# bldc-high-current-2-easyeda.net
KiCad netlist of a schematic drawn in EasyEDA Pro
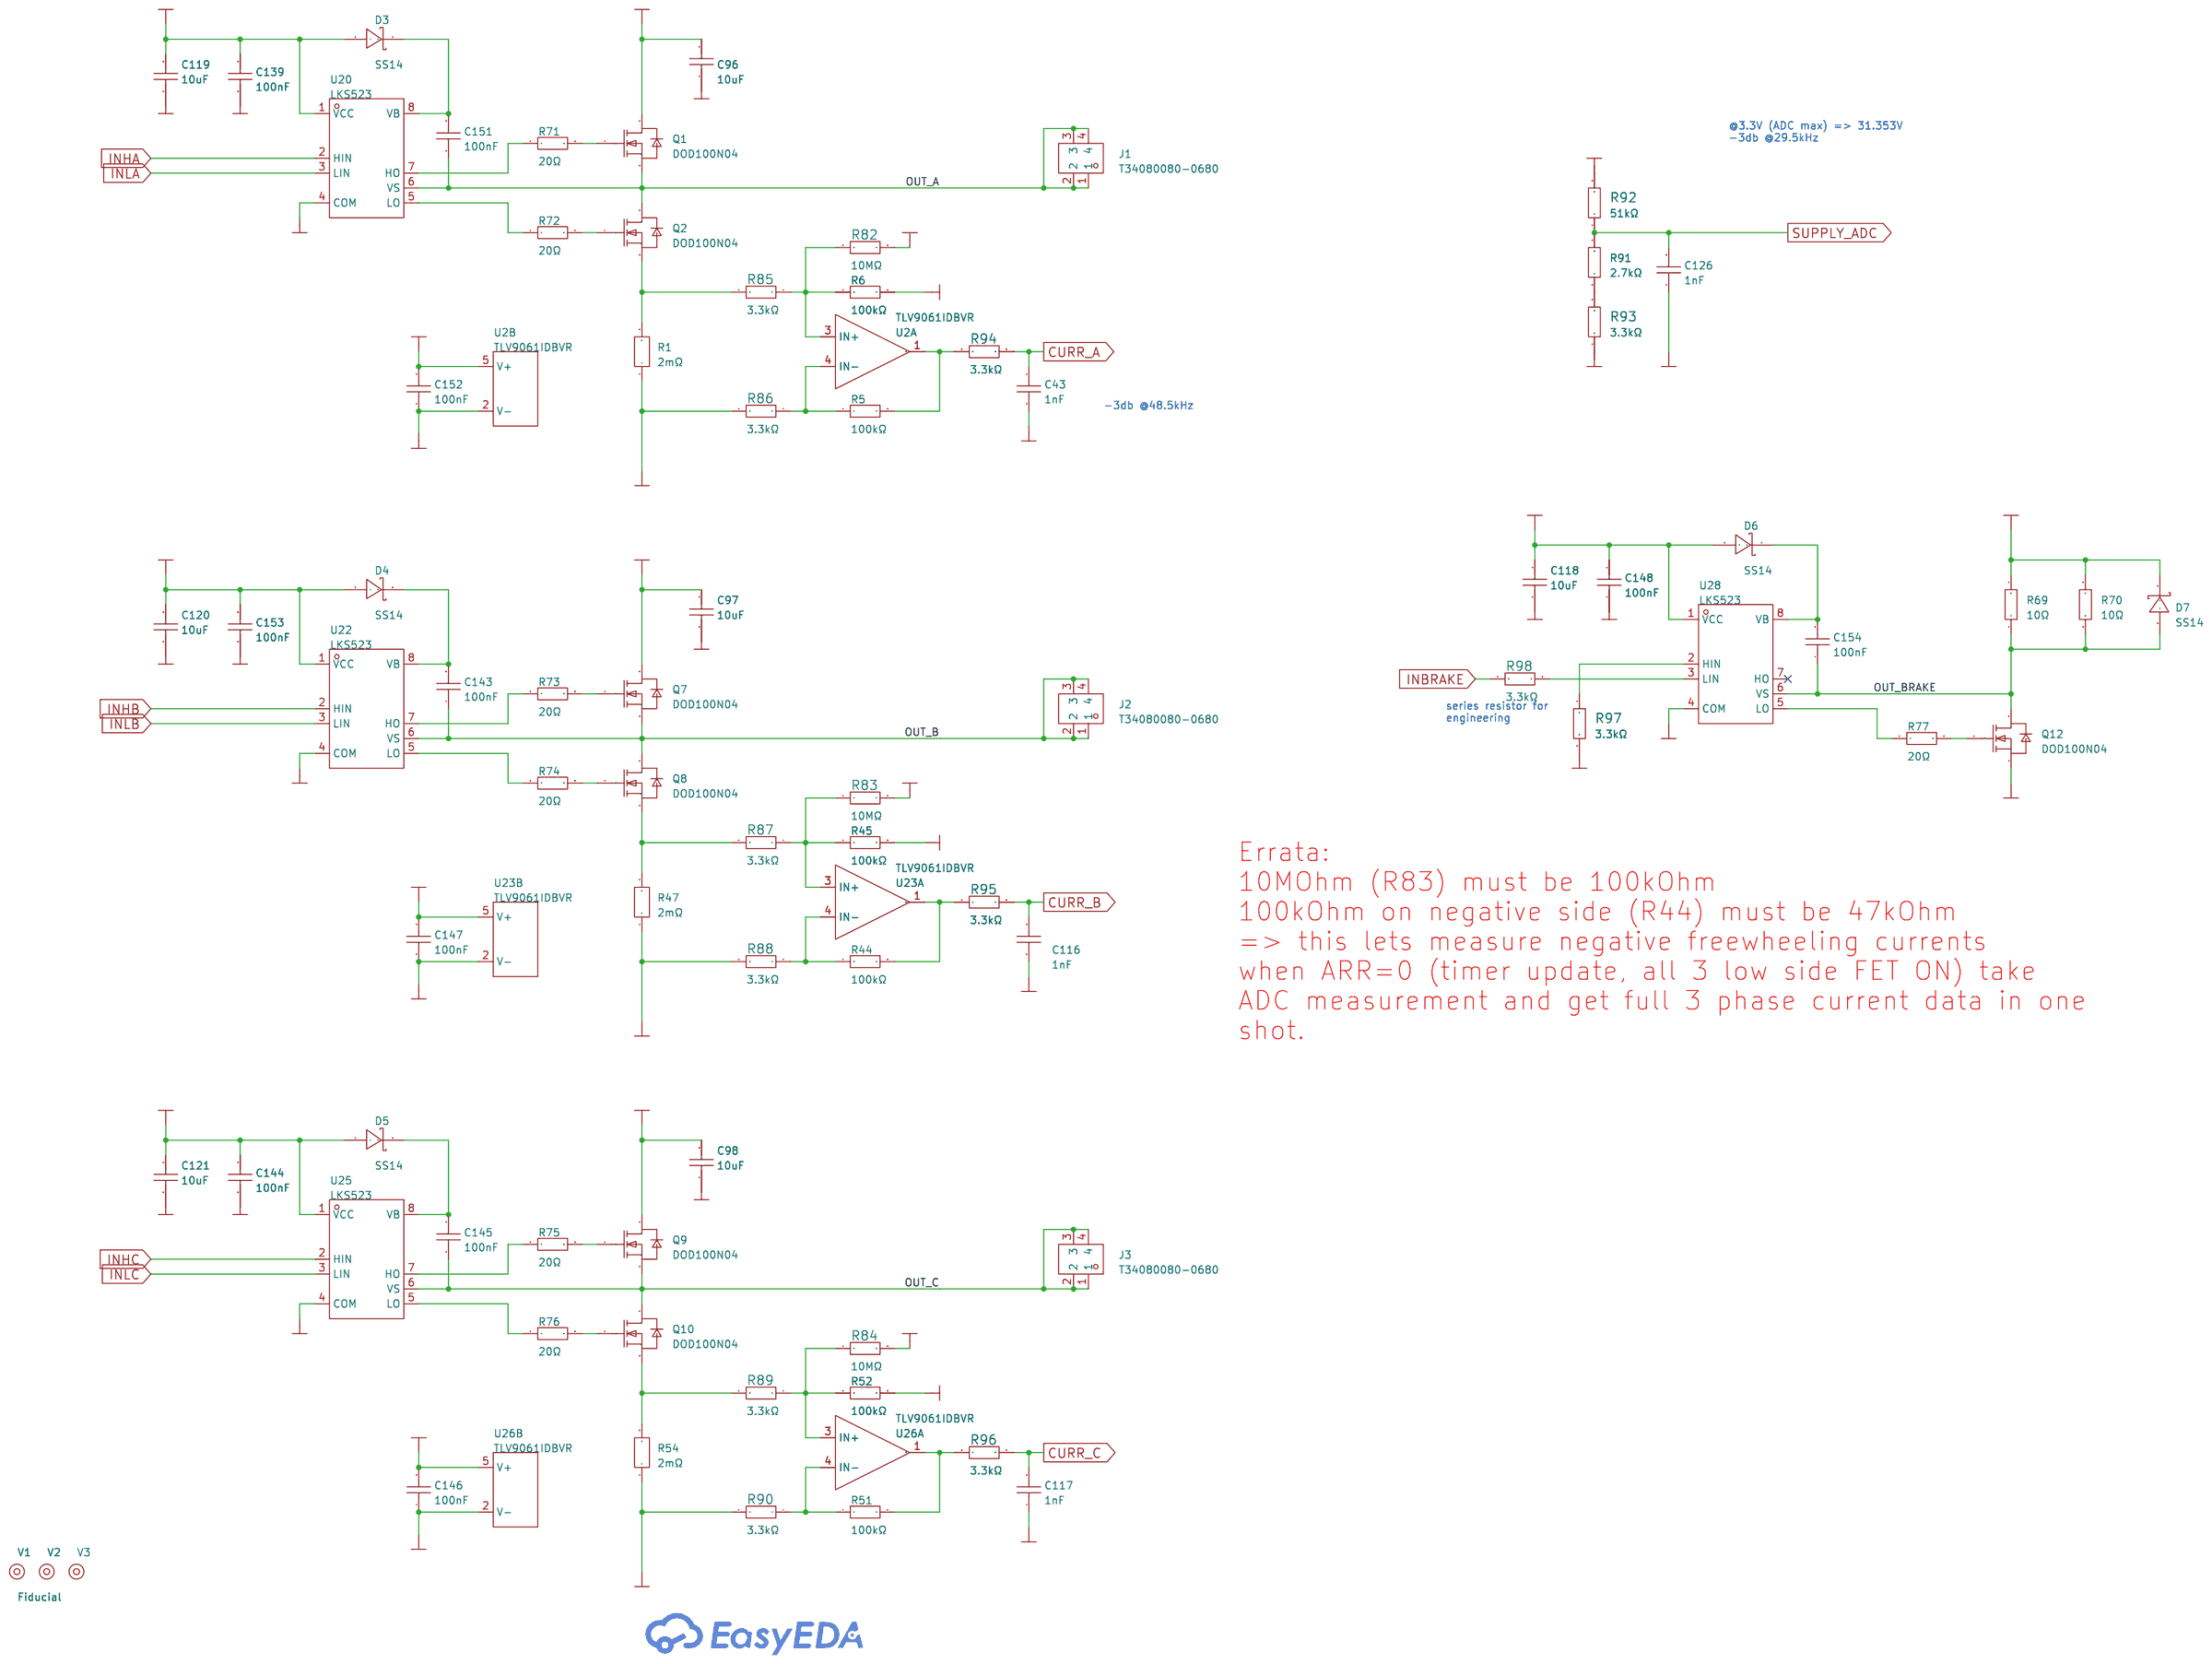
[diagram p0: power stage]
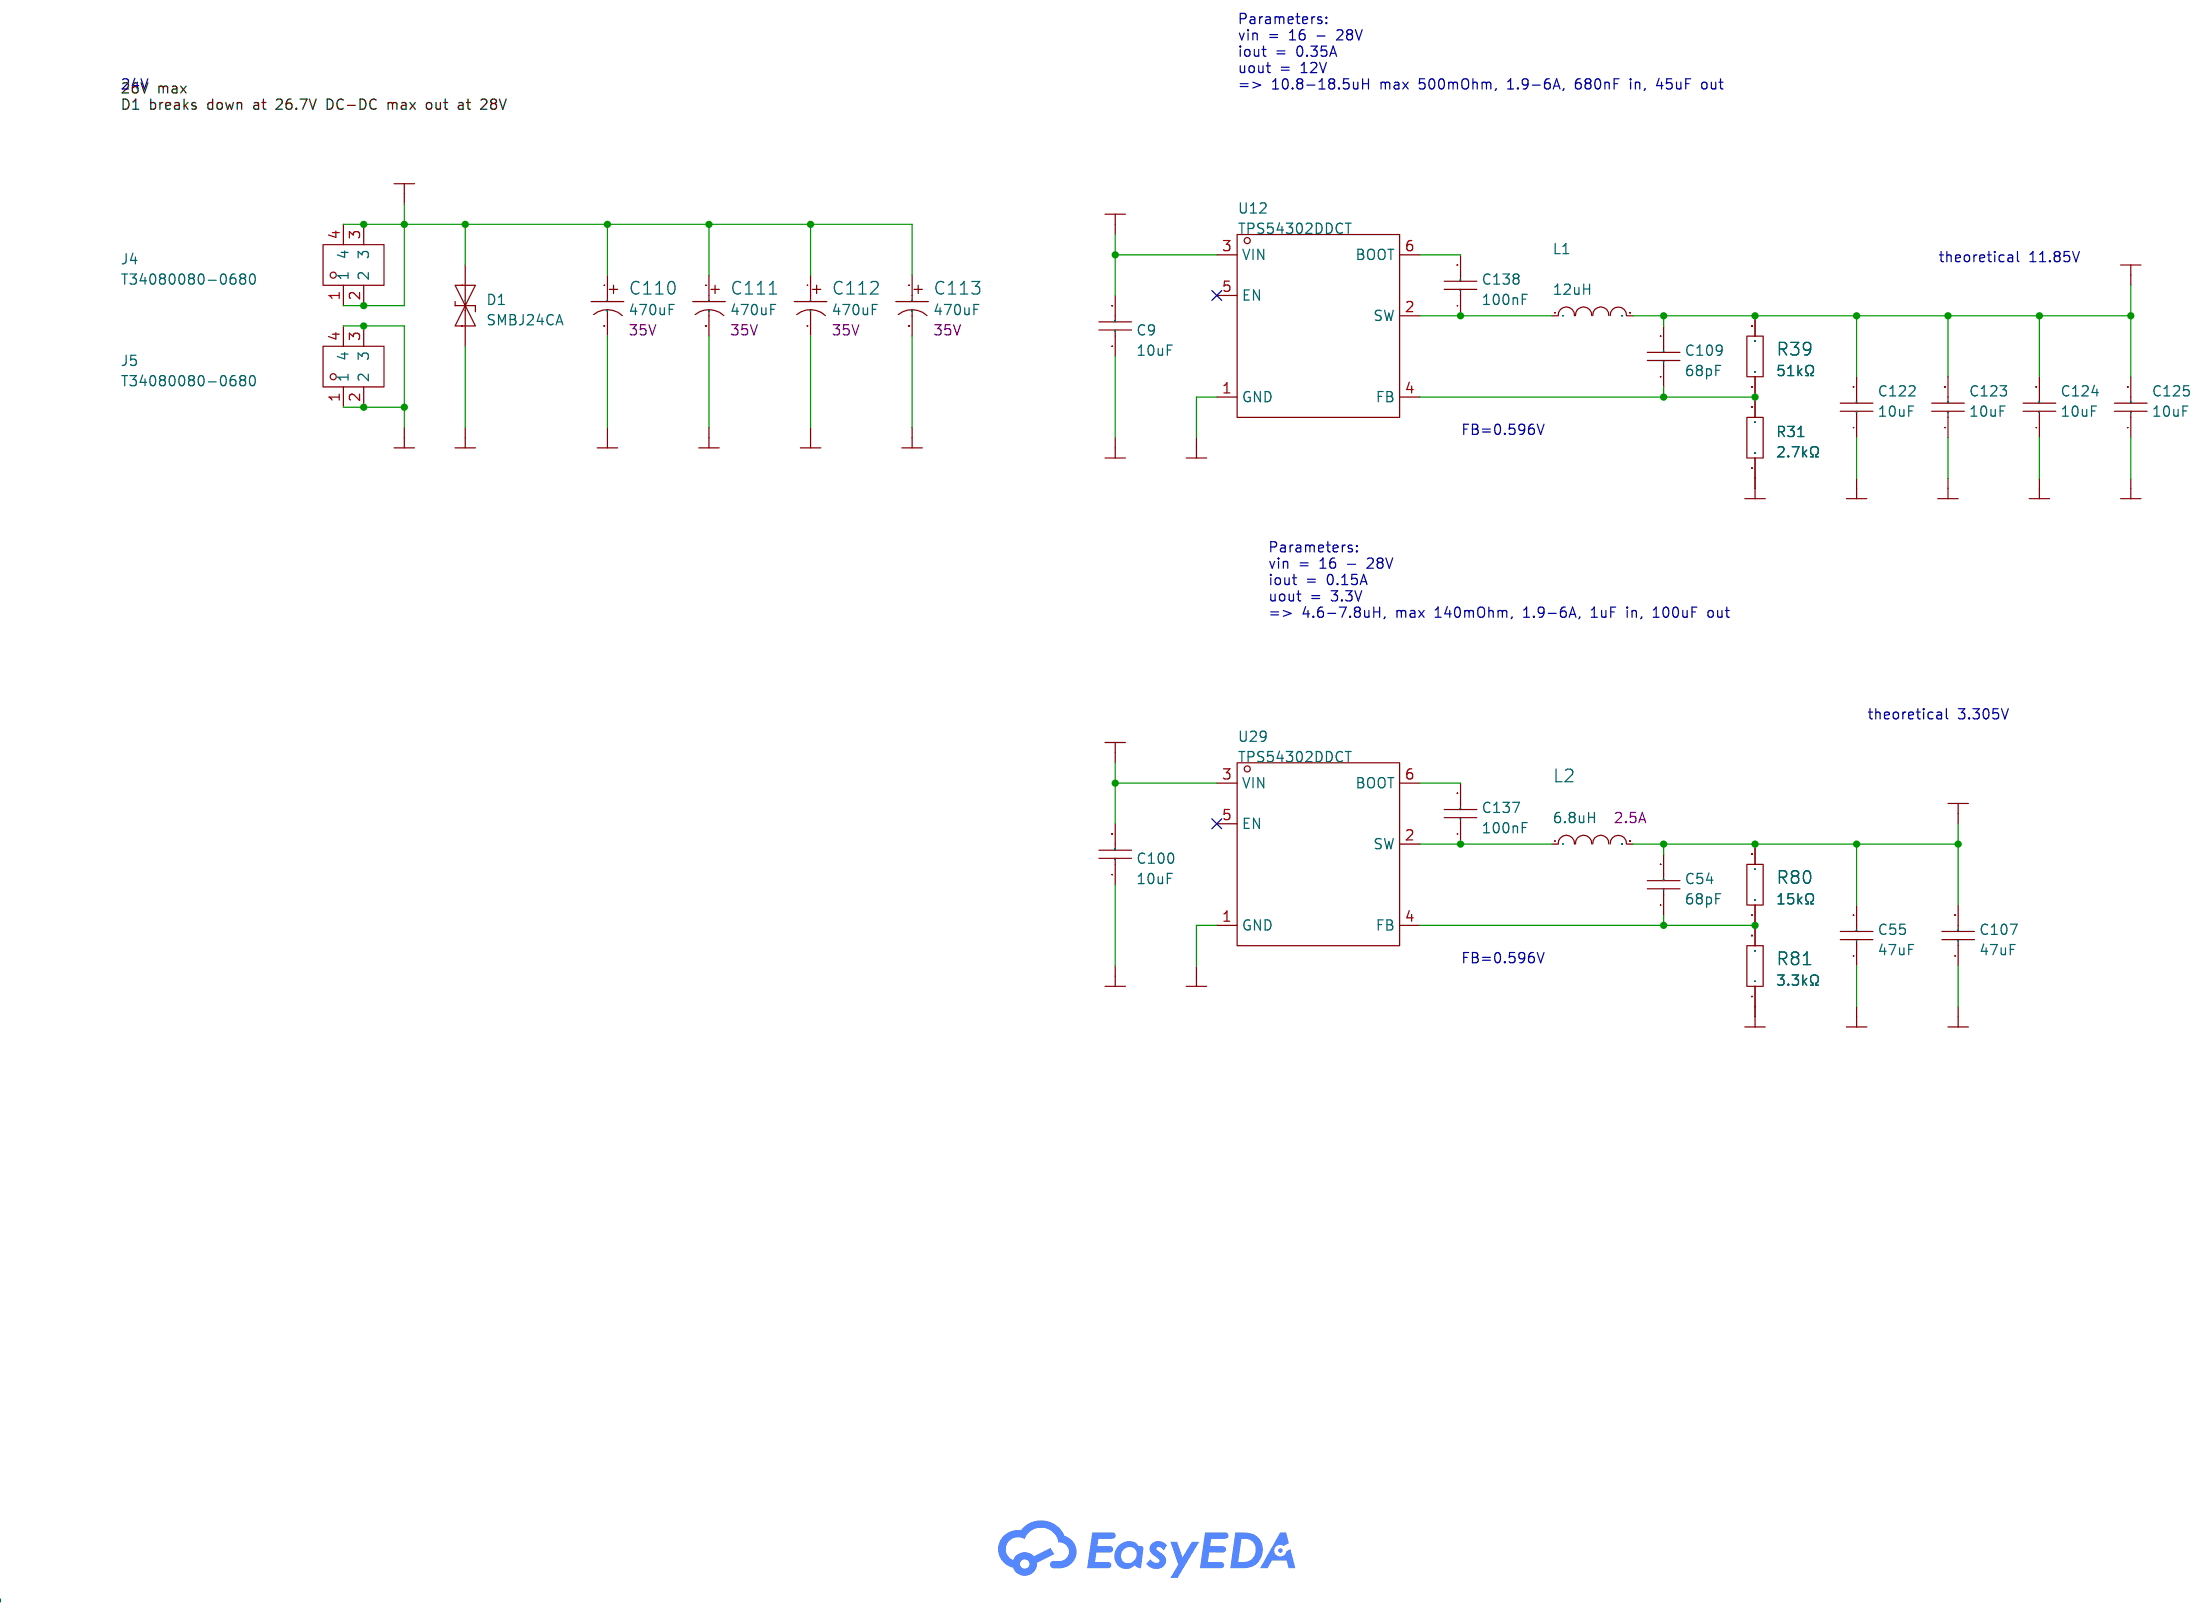
[diagram p1: supply]
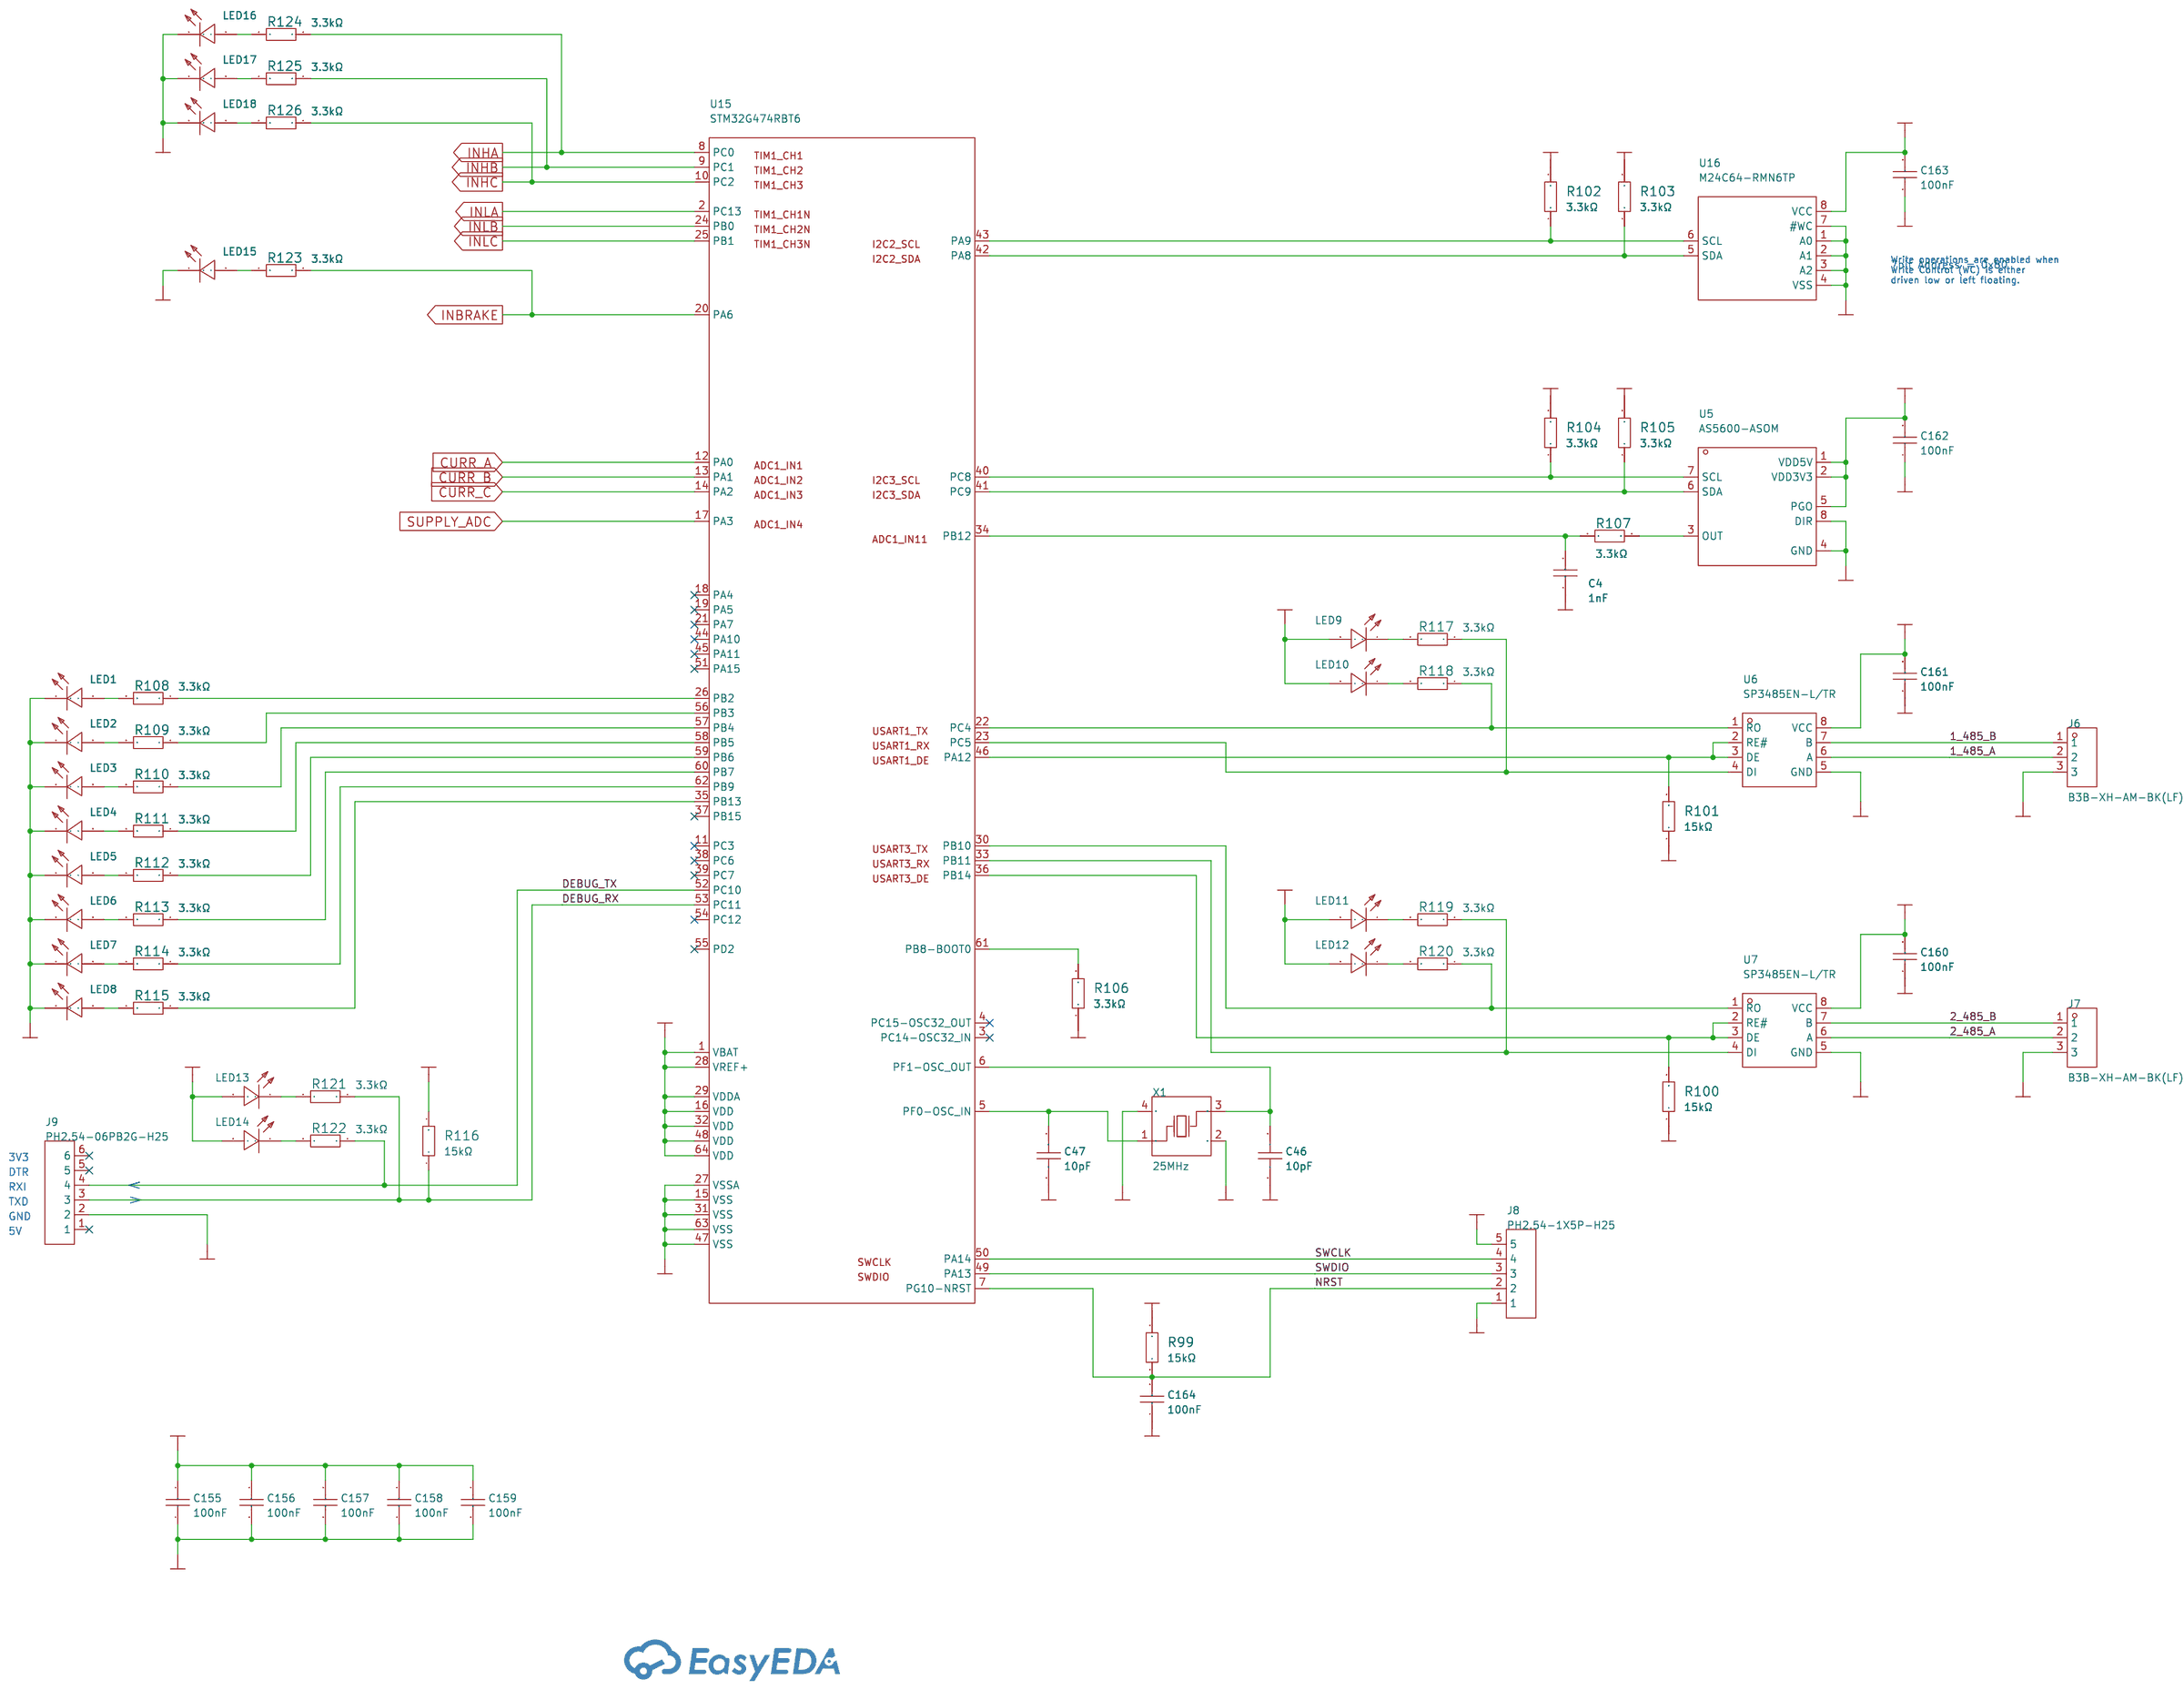
[diagram p2: controller]

(export (version "E")
  (design (tool "Eeschema 10.0.6"))
  (components
    (comp (ref "C43")
      (value "1nF")
      (footprint "easyedapro:C0402")
      (description "Capacitance:1nF Tolerance:±10% Tolerance:±10% Voltage Rating:50V Temperature Coefficient:X7R")
      (fields (field (name "Manufacturer Part") "0402B102K500NT") (field (name "Manufacturer") "FH(风华)"))
      (libsource (lib "easyedapro") (part "0402B102K500NT"))
    )
    (comp (ref "C96")
      (value "10uF")
      (footprint "easyedapro:C1206")
      (description "Capacitance:10uF Tolerance:±10% Tolerance:±10% Voltage Rating:50V Temperature Coefficient:X5R")
      (fields
        (field (name "Manufacturer Part") "CL31A106KBHNNNE")
        (field (name "Manufacturer") "SAMSUNG(三星)")
      )
      (libsource (lib "easyedapro") (part "CL31A106KBHNNNE"))
    )
    (comp (ref "C97")
      (value "10uF")
      (footprint "easyedapro:C1206")
      (description "Capacitance:10uF Tolerance:±10% Tolerance:±10% Voltage Rating:50V Temperature Coefficient:X5R")
      (fields
        (field (name "Manufacturer Part") "CL31A106KBHNNNE")
        (field (name "Manufacturer") "SAMSUNG(三星)")
      )
      (libsource (lib "easyedapro") (part "CL31A106KBHNNNE"))
    )
    (comp (ref "C98")
      (value "10uF")
      (footprint "easyedapro:C1206")
      (description "Capacitance:10uF Tolerance:±10% Tolerance:±10% Voltage Rating:50V Temperature Coefficient:X5R")
      (fields
        (field (name "Manufacturer Part") "CL31A106KBHNNNE")
        (field (name "Manufacturer") "SAMSUNG(三星)")
      )
      (libsource (lib "easyedapro") (part "CL31A106KBHNNNE"))
    )
    (comp (ref "C116")
      (value "1nF")
      (footprint "easyedapro:C0402")
      (description "Capacitance:1nF Tolerance:±10% Tolerance:±10% Voltage Rating:50V Temperature Coefficient:X7R")
      (fields (field (name "Manufacturer Part") "0402B102K500NT") (field (name "Manufacturer") "FH(风华)"))
      (libsource (lib "easyedapro") (part "0402B102K500NT"))
    )
    (comp (ref "C117")
      (value "1nF")
      (footprint "easyedapro:C0402")
      (description "Capacitance:1nF Tolerance:±10% Tolerance:±10% Voltage Rating:50V Temperature Coefficient:X7R")
      (fields (field (name "Manufacturer Part") "0402B102K500NT") (field (name "Manufacturer") "FH(风华)"))
      (libsource (lib "easyedapro") (part "0402B102K500NT"))
    )
    (comp (ref "C118")
      (value "10uF")
      (footprint "easyedapro:C0805")
      (description "Capacitance:10uF Tolerance:±10% Tolerance:±10% Voltage Rating:25V Temperature Coefficient:X5R")
      (fields
        (field (name "Manufacturer Part") "CL21A106KAYNNNE")
        (field (name "Manufacturer") "SAMSUNG(三星)")
      )
      (libsource (lib "easyedapro") (part "CL21A106KAYNNNE"))
    )
    (comp (ref "C119")
      (value "10uF")
      (footprint "easyedapro:C0805")
      (description "Capacitance:10uF Tolerance:±10% Tolerance:±10% Voltage Rating:25V Temperature Coefficient:X5R")
      (fields
        (field (name "Manufacturer Part") "CL21A106KAYNNNE")
        (field (name "Manufacturer") "SAMSUNG(三星)")
      )
      (libsource (lib "easyedapro") (part "CL21A106KAYNNNE"))
    )
    (comp (ref "C120")
      (value "10uF")
      (footprint "easyedapro:C0805")
      (description "Capacitance:10uF Tolerance:±10% Tolerance:±10% Voltage Rating:25V Temperature Coefficient:X5R")
      (fields
        (field (name "Manufacturer Part") "CL21A106KAYNNNE")
        (field (name "Manufacturer") "SAMSUNG(三星)")
      )
      (libsource (lib "easyedapro") (part "CL21A106KAYNNNE"))
    )
    (comp (ref "C121")
      (value "10uF")
      (footprint "easyedapro:C0805")
      (description "Capacitance:10uF Tolerance:±10% Tolerance:±10% Voltage Rating:25V Temperature Coefficient:X5R")
      (fields
        (field (name "Manufacturer Part") "CL21A106KAYNNNE")
        (field (name "Manufacturer") "SAMSUNG(三星)")
      )
      (libsource (lib "easyedapro") (part "CL21A106KAYNNNE"))
    )
    (comp (ref "C126")
      (value "1nF")
      (footprint "easyedapro:C0402")
      (description "Capacitance:1nF Tolerance:±10% Tolerance:±10% Voltage Rating:50V Temperature Coefficient:X7R")
      (fields (field (name "Manufacturer Part") "0402B102K500NT") (field (name "Manufacturer") "FH(风华)"))
      (libsource (lib "easyedapro") (part "0402B102K500NT"))
    )
    (comp (ref "C139")
      (value "100nF")
      (footprint "easyedapro:C0402")
      (description "Capacitance:100nF Tolerance:±10% Tolerance:±10% Voltage Rating:50V Temperature Coefficient:X7R")
      (fields
        (field (name "Manufacturer Part") "CL05B104KB54PNC")
        (field (name "Manufacturer") "SAMSUNG(三星)")
      )
      (libsource (lib "easyedapro") (part "CL05B104KB54PNC"))
    )
    (comp (ref "C143")
      (value "100nF")
      (footprint "easyedapro:C0402")
      (description "Capacitance:100nF Tolerance:±10% Tolerance:±10% Voltage Rating:50V Temperature Coefficient:X7R")
      (fields
        (field (name "Manufacturer Part") "CL05B104KB54PNC")
        (field (name "Manufacturer") "SAMSUNG(三星)")
      )
      (libsource (lib "easyedapro") (part "CL05B104KB54PNC"))
    )
    (comp (ref "C144")
      (value "100nF")
      (footprint "easyedapro:C0402")
      (description "Capacitance:100nF Tolerance:±10% Tolerance:±10% Voltage Rating:50V Temperature Coefficient:X7R")
      (fields
        (field (name "Manufacturer Part") "CL05B104KB54PNC")
        (field (name "Manufacturer") "SAMSUNG(三星)")
      )
      (libsource (lib "easyedapro") (part "CL05B104KB54PNC"))
    )
    (comp (ref "C145")
      (value "100nF")
      (footprint "easyedapro:C0402")
      (description "Capacitance:100nF Tolerance:±10% Tolerance:±10% Voltage Rating:50V Temperature Coefficient:X7R")
      (fields
        (field (name "Manufacturer Part") "CL05B104KB54PNC")
        (field (name "Manufacturer") "SAMSUNG(三星)")
      )
      (libsource (lib "easyedapro") (part "CL05B104KB54PNC"))
    )
    (comp (ref "C146")
      (value "100nF")
      (footprint "easyedapro:C0402")
      (description "Capacitance:100nF Tolerance:±10% Tolerance:±10% Voltage Rating:50V Temperature Coefficient:X7R")
      (fields
        (field (name "Manufacturer Part") "CL05B104KB54PNC")
        (field (name "Manufacturer") "SAMSUNG(三星)")
      )
      (libsource (lib "easyedapro") (part "CL05B104KB54PNC"))
    )
    (comp (ref "C147")
      (value "100nF")
      (footprint "easyedapro:C0402")
      (description "Capacitance:100nF Tolerance:±10% Tolerance:±10% Voltage Rating:50V Temperature Coefficient:X7R")
      (fields
        (field (name "Manufacturer Part") "CL05B104KB54PNC")
        (field (name "Manufacturer") "SAMSUNG(三星)")
      )
      (libsource (lib "easyedapro") (part "CL05B104KB54PNC"))
    )
    (comp (ref "C148")
      (value "100nF")
      (footprint "easyedapro:C0402")
      (description "Capacitance:100nF Tolerance:±10% Tolerance:±10% Voltage Rating:50V Temperature Coefficient:X7R")
      (fields
        (field (name "Manufacturer Part") "CL05B104KB54PNC")
        (field (name "Manufacturer") "SAMSUNG(三星)")
      )
      (libsource (lib "easyedapro") (part "CL05B104KB54PNC"))
    )
    (comp (ref "C151")
      (value "100nF")
      (footprint "easyedapro:C0402")
      (description "Capacitance:100nF Tolerance:±10% Tolerance:±10% Voltage Rating:50V Temperature Coefficient:X7R")
      (fields
        (field (name "Manufacturer Part") "CL05B104KB54PNC")
        (field (name "Manufacturer") "SAMSUNG(三星)")
      )
      (libsource (lib "easyedapro") (part "CL05B104KB54PNC"))
    )
    (comp (ref "C152")
      (value "100nF")
      (footprint "easyedapro:C0402")
      (description "Capacitance:100nF Tolerance:±10% Tolerance:±10% Voltage Rating:50V Temperature Coefficient:X7R")
      (fields
        (field (name "Manufacturer Part") "CL05B104KB54PNC")
        (field (name "Manufacturer") "SAMSUNG(三星)")
      )
      (libsource (lib "easyedapro") (part "CL05B104KB54PNC"))
    )
    (comp (ref "C153")
      (value "100nF")
      (footprint "easyedapro:C0402")
      (description "Capacitance:100nF Tolerance:±10% Tolerance:±10% Voltage Rating:50V Temperature Coefficient:X7R")
      (fields
        (field (name "Manufacturer Part") "CL05B104KB54PNC")
        (field (name "Manufacturer") "SAMSUNG(三星)")
      )
      (libsource (lib "easyedapro") (part "CL05B104KB54PNC"))
    )
    (comp (ref "C154")
      (value "100nF")
      (footprint "easyedapro:C0402")
      (description "Capacitance:100nF Tolerance:±10% Tolerance:±10% Voltage Rating:50V Temperature Coefficient:X7R")
      (fields
        (field (name "Manufacturer Part") "CL05B104KB54PNC")
        (field (name "Manufacturer") "SAMSUNG(三星)")
      )
      (libsource (lib "easyedapro") (part "CL05B104KB54PNC"))
    )
    (comp (ref "D3")
      (value "SS14")
      (footprint "easyedapro:SMA_L4.2-W2.6-LS5.0-RD_1")
      (fields (field (name "Manufacturer") "MDD(辰达半导体)"))
      (libsource (lib "easyedapro") (part "SS14"))
    )
    (comp (ref "D4")
      (value "SS14")
      (footprint "easyedapro:SMA_L4.2-W2.6-LS5.0-RD_1")
      (fields (field (name "Manufacturer") "MDD(辰达半导体)"))
      (libsource (lib "easyedapro") (part "SS14"))
    )
    (comp (ref "D5")
      (value "SS14")
      (footprint "easyedapro:SMA_L4.2-W2.6-LS5.0-RD_1")
      (fields (field (name "Manufacturer") "MDD(辰达半导体)"))
      (libsource (lib "easyedapro") (part "SS14"))
    )
    (comp (ref "D6")
      (value "SS14")
      (footprint "easyedapro:SMA_L4.2-W2.6-LS5.0-RD_1")
      (fields (field (name "Manufacturer") "MDD(辰达半导体)"))
      (libsource (lib "easyedapro") (part "SS14"))
    )
    (comp (ref "D7")
      (value "SS14")
      (footprint "easyedapro:SMA_L4.2-W2.6-LS5.0-RD_1")
      (fields (field (name "Manufacturer") "MDD(辰达半导体)"))
      (libsource (lib "easyedapro") (part "SS14"))
    )
    (comp (ref "J1")
      (value "T34080080-0680")
      (footprint "easyedapro:CONN-TH_T34080080-0680")
      (fields (field (name "Manufacturer") "XFCN(兴飞)"))
      (libsource (lib "easyedapro") (part "T34080080-0680"))
    )
    (comp (ref "J2")
      (value "T34080080-0680")
      (footprint "easyedapro:CONN-TH_T34080080-0680")
      (description "Screw Hole Size:M3 Number of Leg:4")
      (fields (field (name "Manufacturer") "XFCN(兴飞)"))
      (libsource (lib "easyedapro") (part "T34080080-0680"))
    )
    (comp (ref "J3")
      (value "T34080080-0680")
      (footprint "easyedapro:CONN-TH_T34080080-0680")
      (description "Screw Hole Size:M3 Number of Leg:4")
      (fields (field (name "Manufacturer") "XFCN(兴飞)"))
      (libsource (lib "easyedapro") (part "T34080080-0680"))
    )
    (comp (ref "Q1")
      (value "DOD100N04")
      (footprint "easyedapro:TO-252-2_L6.6-W6.2-P4.57-LS10.1-BR-CW")
      (fields (field (name "Manufacturer") "DOINGTER(杜因特)"))
      (libsource (lib "easyedapro") (part "DOD100N04"))
    )
    (comp (ref "Q2")
      (value "DOD100N04")
      (footprint "easyedapro:TO-252-2_L6.6-W6.2-P4.57-LS10.1-BR-CW")
      (fields (field (name "Manufacturer") "DOINGTER(杜因特)"))
      (libsource (lib "easyedapro") (part "DOD100N04"))
    )
    (comp (ref "Q7")
      (value "DOD100N04")
      (footprint "easyedapro:TO-252-2_L6.6-W6.2-P4.57-LS10.1-BR-CW")
      (fields (field (name "Manufacturer") "DOINGTER(杜因特)"))
      (libsource (lib "easyedapro") (part "DOD100N04"))
    )
    (comp (ref "Q8")
      (value "DOD100N04")
      (footprint "easyedapro:TO-252-2_L6.6-W6.2-P4.57-LS10.1-BR-CW")
      (fields (field (name "Manufacturer") "DOINGTER(杜因特)"))
      (libsource (lib "easyedapro") (part "DOD100N04"))
    )
    (comp (ref "Q9")
      (value "DOD100N04")
      (footprint "easyedapro:TO-252-2_L6.6-W6.2-P4.57-LS10.1-BR-CW")
      (fields (field (name "Manufacturer") "DOINGTER(杜因特)"))
      (libsource (lib "easyedapro") (part "DOD100N04"))
    )
    (comp (ref "Q10")
      (value "DOD100N04")
      (footprint "easyedapro:TO-252-2_L6.6-W6.2-P4.57-LS10.1-BR-CW")
      (fields (field (name "Manufacturer") "DOINGTER(杜因特)"))
      (libsource (lib "easyedapro") (part "DOD100N04"))
    )
    (comp (ref "Q12")
      (value "DOD100N04")
      (footprint "easyedapro:TO-252-2_L6.6-W6.2-P4.57-LS10.1-BR-CW")
      (fields (field (name "Manufacturer") "DOINGTER(杜因特)"))
      (libsource (lib "easyedapro") (part "DOD100N04"))
    )
    (comp (ref "R1")
      (value "2mΩ")
      (footprint "easyedapro:RES-SMD_L6.4-W3.2-1")
      (fields
        (field (name "Manufacturer Part") "HoLLR2512-3W-2mR-1%")
        (field (name "Manufacturer") "Milliohm(毫欧)")
      )
      (libsource (lib "easyedapro") (part "HOLLR2512-3W-2MR-1%"))
    )
    (comp (ref "R5")
      (value "100kΩ")
      (footprint "easyedapro:R0603")
      (fields
        (field (name "Manufacturer Part") "0603WAF1003T5E")
        (field (name "Manufacturer") "UNI-ROYAL(厚声)")
      )
      (libsource (lib "easyedapro") (part "0603WAF1003T5E"))
    )
    (comp (ref "R6")
      (value "100kΩ")
      (footprint "easyedapro:R0603")
      (fields
        (field (name "Manufacturer Part") "0603WAF1003T5E")
        (field (name "Manufacturer") "UNI-ROYAL(厚声)")
      )
      (libsource (lib "easyedapro") (part "0603WAF1003T5E"))
    )
    (comp (ref "R44")
      (value "100kΩ")
      (footprint "easyedapro:R0603")
      (fields
        (field (name "Manufacturer Part") "0603WAF1003T5E")
        (field (name "Manufacturer") "UNI-ROYAL(厚声)")
      )
      (libsource (lib "easyedapro") (part "0603WAF1003T5E"))
    )
    (comp (ref "R45")
      (value "100kΩ")
      (footprint "easyedapro:R0603")
      (fields
        (field (name "Manufacturer Part") "0603WAF1003T5E")
        (field (name "Manufacturer") "UNI-ROYAL(厚声)")
      )
      (libsource (lib "easyedapro") (part "0603WAF1003T5E"))
    )
    (comp (ref "R47")
      (value "2mΩ")
      (footprint "easyedapro:RES-SMD_L6.4-W3.2-1")
      (fields
        (field (name "Manufacturer Part") "HoLLR2512-3W-2mR-1%")
        (field (name "Manufacturer") "Milliohm(毫欧)")
      )
      (libsource (lib "easyedapro") (part "HOLLR2512-3W-2MR-1%"))
    )
    (comp (ref "R51")
      (value "100kΩ")
      (footprint "easyedapro:R0603")
      (fields
        (field (name "Manufacturer Part") "0603WAF1003T5E")
        (field (name "Manufacturer") "UNI-ROYAL(厚声)")
      )
      (libsource (lib "easyedapro") (part "0603WAF1003T5E"))
    )
    (comp (ref "R52")
      (value "100kΩ")
      (footprint "easyedapro:R0603")
      (fields
        (field (name "Manufacturer Part") "0603WAF1003T5E")
        (field (name "Manufacturer") "UNI-ROYAL(厚声)")
      )
      (libsource (lib "easyedapro") (part "0603WAF1003T5E"))
    )
    (comp (ref "R54")
      (value "2mΩ")
      (footprint "easyedapro:RES-SMD_L6.4-W3.2-1")
      (fields
        (field (name "Manufacturer Part") "HoLLR2512-3W-2mR-1%")
        (field (name "Manufacturer") "Milliohm(毫欧)")
      )
      (libsource (lib "easyedapro") (part "HOLLR2512-3W-2MR-1%"))
    )
    (comp (ref "R69")
      (value "10Ω")
      (footprint "easyedapro:RES-TH_BD8.0-L24.5-P28.50-D0.8")
      (fields (field (name "Manufacturer Part") "KNP5W-10Ω±5% T") (field (name "Manufacturer") "CCO(千志电子)"))
      (libsource (lib "easyedapro") (part "KNP5W-10Ω±5% T"))
    )
    (comp (ref "R70")
      (value "10Ω")
      (footprint "easyedapro:RES-TH_BD8.0-L24.5-P28.50-D0.8")
      (fields (field (name "Manufacturer Part") "KNP5W-10Ω±5% T") (field (name "Manufacturer") "CCO(千志电子)"))
      (libsource (lib "easyedapro") (part "KNP5W-10Ω±5% T"))
    )
    (comp (ref "R71")
      (value "20Ω")
      (footprint "easyedapro:R0805")
      (fields
        (field (name "Manufacturer Part") "0805W8F200JT5E")
        (field (name "Manufacturer") "UNI-ROYAL(厚声)")
      )
      (libsource (lib "easyedapro") (part "0805W8F200JT5E"))
    )
    (comp (ref "R72")
      (value "20Ω")
      (footprint "easyedapro:R0805")
      (fields
        (field (name "Manufacturer Part") "0805W8F200JT5E")
        (field (name "Manufacturer") "UNI-ROYAL(厚声)")
      )
      (libsource (lib "easyedapro") (part "0805W8F200JT5E"))
    )
    (comp (ref "R73")
      (value "20Ω")
      (footprint "easyedapro:R0805")
      (fields
        (field (name "Manufacturer Part") "0805W8F200JT5E")
        (field (name "Manufacturer") "UNI-ROYAL(厚声)")
      )
      (libsource (lib "easyedapro") (part "0805W8F200JT5E"))
    )
    (comp (ref "R74")
      (value "20Ω")
      (footprint "easyedapro:R0805")
      (fields
        (field (name "Manufacturer Part") "0805W8F200JT5E")
        (field (name "Manufacturer") "UNI-ROYAL(厚声)")
      )
      (libsource (lib "easyedapro") (part "0805W8F200JT5E"))
    )
    (comp (ref "R75")
      (value "20Ω")
      (footprint "easyedapro:R0805")
      (fields
        (field (name "Manufacturer Part") "0805W8F200JT5E")
        (field (name "Manufacturer") "UNI-ROYAL(厚声)")
      )
      (libsource (lib "easyedapro") (part "0805W8F200JT5E"))
    )
    (comp (ref "R76")
      (value "20Ω")
      (footprint "easyedapro:R0805")
      (fields
        (field (name "Manufacturer Part") "0805W8F200JT5E")
        (field (name "Manufacturer") "UNI-ROYAL(厚声)")
      )
      (libsource (lib "easyedapro") (part "0805W8F200JT5E"))
    )
    (comp (ref "R77")
      (value "20Ω")
      (footprint "easyedapro:R0805")
      (fields
        (field (name "Manufacturer Part") "0805W8F200JT5E")
        (field (name "Manufacturer") "UNI-ROYAL(厚声)")
      )
      (libsource (lib "easyedapro") (part "0805W8F200JT5E"))
    )
    (comp (ref "R82")
      (value "10MΩ")
      (footprint "easyedapro:R0603")
      (fields
        (field (name "Manufacturer Part") "0603WAF1005T5E")
        (field (name "Manufacturer") "UNI-ROYAL(厚声)")
      )
      (libsource (lib "easyedapro") (part "0603WAF1005T5E"))
    )
    (comp (ref "R83")
      (value "10MΩ")
      (footprint "easyedapro:R0603")
      (fields
        (field (name "Manufacturer Part") "0603WAF1005T5E")
        (field (name "Manufacturer") "UNI-ROYAL(厚声)")
      )
      (libsource (lib "easyedapro") (part "0603WAF1005T5E"))
    )
    (comp (ref "R84")
      (value "10MΩ")
      (footprint "easyedapro:R0603")
      (fields
        (field (name "Manufacturer Part") "0603WAF1005T5E")
        (field (name "Manufacturer") "UNI-ROYAL(厚声)")
      )
      (libsource (lib "easyedapro") (part "0603WAF1005T5E"))
    )
    (comp (ref "R85")
      (value "3.3kΩ")
      (footprint "easyedapro:R0402")
      (fields
        (field (name "Manufacturer Part") "0402WGF3301TCE")
        (field (name "Manufacturer") "UNI-ROYAL(厚声)")
      )
      (libsource (lib "easyedapro") (part "0402WGF3301TCE"))
    )
    (comp (ref "R86")
      (value "3.3kΩ")
      (footprint "easyedapro:R0402")
      (fields
        (field (name "Manufacturer Part") "0402WGF3301TCE")
        (field (name "Manufacturer") "UNI-ROYAL(厚声)")
      )
      (libsource (lib "easyedapro") (part "0402WGF3301TCE"))
    )
    (comp (ref "R87")
      (value "3.3kΩ")
      (footprint "easyedapro:R0402")
      (fields
        (field (name "Manufacturer Part") "0402WGF3301TCE")
        (field (name "Manufacturer") "UNI-ROYAL(厚声)")
      )
      (libsource (lib "easyedapro") (part "0402WGF3301TCE"))
    )
    (comp (ref "R88")
      (value "3.3kΩ")
      (footprint "easyedapro:R0402")
      (fields
        (field (name "Manufacturer Part") "0402WGF3301TCE")
        (field (name "Manufacturer") "UNI-ROYAL(厚声)")
      )
      (libsource (lib "easyedapro") (part "0402WGF3301TCE"))
    )
    (comp (ref "R89")
      (value "3.3kΩ")
      (footprint "easyedapro:R0402")
      (fields
        (field (name "Manufacturer Part") "0402WGF3301TCE")
        (field (name "Manufacturer") "UNI-ROYAL(厚声)")
      )
      (libsource (lib "easyedapro") (part "0402WGF3301TCE"))
    )
    (comp (ref "R90")
      (value "3.3kΩ")
      (footprint "easyedapro:R0402")
      (fields
        (field (name "Manufacturer Part") "0402WGF3301TCE")
        (field (name "Manufacturer") "UNI-ROYAL(厚声)")
      )
      (libsource (lib "easyedapro") (part "0402WGF3301TCE"))
    )
    (comp (ref "R91")
      (value "2.7kΩ")
      (footprint "easyedapro:R0603")
      (fields
        (field (name "Manufacturer Part") "0603WAF2701T5E")
        (field (name "Manufacturer") "UNI-ROYAL(厚声)")
      )
      (libsource (lib "easyedapro") (part "0603WAF2701T5E"))
    )
    (comp (ref "R92")
      (value "51kΩ")
      (footprint "easyedapro:R0402")
      (fields
        (field (name "Manufacturer Part") "0402WGF5102TCE")
        (field (name "Manufacturer") "UNI-ROYAL(厚声)")
      )
      (libsource (lib "easyedapro") (part "0402WGF5102TCE"))
    )
    (comp (ref "R93")
      (value "3.3kΩ")
      (footprint "easyedapro:R0402")
      (fields
        (field (name "Manufacturer Part") "0402WGF3301TCE")
        (field (name "Manufacturer") "UNI-ROYAL(厚声)")
      )
      (libsource (lib "easyedapro") (part "0402WGF3301TCE"))
    )
    (comp (ref "R94")
      (value "3.3kΩ")
      (footprint "easyedapro:R0402")
      (fields
        (field (name "Manufacturer Part") "0402WGF3301TCE")
        (field (name "Manufacturer") "UNI-ROYAL(厚声)")
      )
      (libsource (lib "easyedapro") (part "0402WGF3301TCE"))
    )
    (comp (ref "R95")
      (value "3.3kΩ")
      (footprint "easyedapro:R0402")
      (fields
        (field (name "Manufacturer Part") "0402WGF3301TCE")
        (field (name "Manufacturer") "UNI-ROYAL(厚声)")
      )
      (libsource (lib "easyedapro") (part "0402WGF3301TCE"))
    )
    (comp (ref "R96")
      (value "3.3kΩ")
      (footprint "easyedapro:R0402")
      (fields
        (field (name "Manufacturer Part") "0402WGF3301TCE")
        (field (name "Manufacturer") "UNI-ROYAL(厚声)")
      )
      (libsource (lib "easyedapro") (part "0402WGF3301TCE"))
    )
    (comp (ref "R97")
      (value "3.3kΩ")
      (footprint "easyedapro:R0402")
      (fields
        (field (name "Manufacturer Part") "0402WGF3301TCE")
        (field (name "Manufacturer") "UNI-ROYAL(厚声)")
      )
      (libsource (lib "easyedapro") (part "0402WGF3301TCE"))
    )
    (comp (ref "R98")
      (value "3.3kΩ")
      (footprint "easyedapro:R0402")
      (fields
        (field (name "Manufacturer Part") "0402WGF3301TCE")
        (field (name "Manufacturer") "UNI-ROYAL(厚声)")
      )
      (libsource (lib "easyedapro") (part "0402WGF3301TCE"))
    )
    (comp (ref "U2")
      (value "TLV9061IDBVR")
      (footprint "easyedapro:SOT-23-5_L3.0-W1.7-P0.95-LS2.8-BL")
      (fields (field (name "Manufacturer") "TI(德州仪器)"))
      (libsource (lib "easyedapro") (part "TLV9061IDBVR"))
    )
    (comp (ref "U20")
      (value "LKS523")
      (footprint "easyedapro:SOP-8_L4.9-W3.9-P1.27-LS6.0-BL")
      (fields (field (name "Manufacturer") "LINKOSEMI(凌鸥创芯)"))
      (libsource (lib "easyedapro") (part "LKS523"))
    )
    (comp (ref "U22")
      (value "LKS523")
      (footprint "easyedapro:SOP-8_L4.9-W3.9-P1.27-LS6.0-BL")
      (fields (field (name "Manufacturer") "LINKOSEMI(凌鸥创芯)"))
      (libsource (lib "easyedapro") (part "LKS523"))
    )
    (comp (ref "U23")
      (value "TLV9061IDBVR")
      (footprint "easyedapro:SOT-23-5_L3.0-W1.7-P0.95-LS2.8-BL")
      (fields (field (name "Manufacturer") "TI(德州仪器)"))
      (libsource (lib "easyedapro") (part "TLV9061IDBVR"))
    )
    (comp (ref "U25")
      (value "LKS523")
      (footprint "easyedapro:SOP-8_L4.9-W3.9-P1.27-LS6.0-BL")
      (fields (field (name "Manufacturer") "LINKOSEMI(凌鸥创芯)"))
      (libsource (lib "easyedapro") (part "LKS523"))
    )
    (comp (ref "U26")
      (value "TLV9061IDBVR")
      (footprint "easyedapro:SOT-23-5_L3.0-W1.7-P0.95-LS2.8-BL")
      (fields (field (name "Manufacturer") "TI(德州仪器)"))
      (libsource (lib "easyedapro") (part "TLV9061IDBVR"))
    )
    (comp (ref "U28")
      (value "LKS523")
      (footprint "easyedapro:SOP-8_L4.9-W3.9-P1.27-LS6.0-BL")
      (fields (field (name "Manufacturer") "LINKOSEMI(凌鸥创芯)"))
      (libsource (lib "easyedapro") (part "LKS523"))
    )
    (comp (ref "V1")
      (value "Fiducial")
      (footprint "easyedapro:Fiducial:Fiducial_0.5mm_Mask1mm")
      (libsource (lib "easyedapro") (part "Mechanical_Fiducial"))
    )
    (comp (ref "V2")
      (value "Fiducial")
      (footprint "easyedapro:Fiducial:Fiducial_0.5mm_Mask1mm")
      (libsource (lib "easyedapro") (part "Mechanical_Fiducial"))
    )
    (comp (ref "V3")
      (value "Fiducial")
      (footprint "easyedapro:Fiducial:Fiducial_0.5mm_Mask1mm")
      (libsource (lib "easyedapro") (part "Mechanical_Fiducial"))
    )
    (comp (ref "C9")
      (value "10uF")
      (footprint "easyedapro:C1206")
      (description "Capacitance:10uF Tolerance:±10% Tolerance:±10% Voltage Rating:50V Temperature Coefficient:X5R")
      (fields
        (field (name "Manufacturer Part") "CL31A106KBHNNNE")
        (field (name "Manufacturer") "SAMSUNG(三星)")
      )
      (libsource (lib "easyedapro") (part "CL31A106KBHNNNE"))
    )
    (comp (ref "C54")
      (value "68pF")
      (footprint "easyedapro:C0603")
      (description "Capacitance:68pF Tolerance:±5% Tolerance:±5% Voltage Rating:50V Temperature Coefficient:C0G")
      (fields (field (name "Manufacturer Part") "0603CG680J500NT") (field (name "Manufacturer") "FH(风华)"))
      (libsource (lib "easyedapro") (part "0603CG680J500NT"))
    )
    (comp (ref "C55")
      (value "47uF")
      (footprint "easyedapro:C0805")
      (description "Capacitance:47uF Tolerance:±20% Tolerance:±20% Voltage Rating:6.3V Temperature Coefficient:X5R")
      (fields
        (field (name "Manufacturer Part") "CL21A476MQYNNNE")
        (field (name "Manufacturer") "SAMSUNG(三星)")
      )
      (libsource (lib "easyedapro") (part "CL21A476MQYNNNE"))
    )
    (comp (ref "C100")
      (value "10uF")
      (footprint "easyedapro:C1206")
      (description "Capacitance:10uF Tolerance:±10% Tolerance:±10% Voltage Rating:50V Temperature Coefficient:X5R")
      (fields
        (field (name "Manufacturer Part") "CL31A106KBHNNNE")
        (field (name "Manufacturer") "SAMSUNG(三星)")
      )
      (libsource (lib "easyedapro") (part "CL31A106KBHNNNE"))
    )
    (comp (ref "C107")
      (value "47uF")
      (footprint "easyedapro:C0805")
      (description "Capacitance:47uF Tolerance:±20% Tolerance:±20% Voltage Rating:6.3V Temperature Coefficient:X5R")
      (fields
        (field (name "Manufacturer Part") "CL21A476MQYNNNE")
        (field (name "Manufacturer") "SAMSUNG(三星)")
      )
      (libsource (lib "easyedapro") (part "CL21A476MQYNNNE"))
    )
    (comp (ref "C109")
      (value "68pF")
      (footprint "easyedapro:C0603")
      (description "Capacitance:68pF Tolerance:±5% Tolerance:±5% Voltage Rating:50V Temperature Coefficient:C0G")
      (fields (field (name "Manufacturer Part") "0603CG680J500NT") (field (name "Manufacturer") "FH(风华)"))
      (libsource (lib "easyedapro") (part "0603CG680J500NT"))
    )
    (comp (ref "C110")
      (value "470uF")
      (footprint "easyedapro:CAP-SMD_BD10.0-L10.3-W10.3-FD")
      (fields
        (field (name "Manufacturer Part") "RVT1V471M1010")
        (field (name "Manufacturer") "HONOR(荣誉)")
        (field (name "Rated Voltage") "35V")
      )
      (libsource (lib "easyedapro") (part "RVT1V471M1010"))
    )
    (comp (ref "C111")
      (value "470uF")
      (footprint "easyedapro:CAP-SMD_BD10.0-L10.3-W10.3-FD")
      (fields
        (field (name "Manufacturer Part") "RVT1V471M1010")
        (field (name "Manufacturer") "HONOR(荣誉)")
        (field (name "Rated Voltage") "35V")
      )
      (libsource (lib "easyedapro") (part "RVT1V471M1010"))
    )
    (comp (ref "C112")
      (value "470uF")
      (footprint "easyedapro:CAP-SMD_BD10.0-L10.3-W10.3-FD")
      (fields
        (field (name "Manufacturer Part") "RVT1V471M1010")
        (field (name "Manufacturer") "HONOR(荣誉)")
        (field (name "Rated Voltage") "35V")
      )
      (libsource (lib "easyedapro") (part "RVT1V471M1010"))
    )
    (comp (ref "C113")
      (value "470uF")
      (footprint "easyedapro:CAP-SMD_BD10.0-L10.3-W10.3-FD")
      (fields
        (field (name "Manufacturer Part") "RVT1V471M1010")
        (field (name "Manufacturer") "HONOR(荣誉)")
        (field (name "Rated Voltage") "35V")
      )
      (libsource (lib "easyedapro") (part "RVT1V471M1010"))
    )
    (comp (ref "C122")
      (value "10uF")
      (footprint "easyedapro:C0805")
      (description "Capacitance:10uF Tolerance:±10% Tolerance:±10% Voltage Rating:25V Temperature Coefficient:X5R")
      (fields
        (field (name "Manufacturer Part") "CL21A106KAYNNNE")
        (field (name "Manufacturer") "SAMSUNG(三星)")
      )
      (libsource (lib "easyedapro") (part "CL21A106KAYNNNE"))
    )
    (comp (ref "C123")
      (value "10uF")
      (footprint "easyedapro:C0805")
      (description "Capacitance:10uF Tolerance:±10% Tolerance:±10% Voltage Rating:25V Temperature Coefficient:X5R")
      (fields
        (field (name "Manufacturer Part") "CL21A106KAYNNNE")
        (field (name "Manufacturer") "SAMSUNG(三星)")
      )
      (libsource (lib "easyedapro") (part "CL21A106KAYNNNE"))
    )
    (comp (ref "C124")
      (value "10uF")
      (footprint "easyedapro:C0805")
      (description "Capacitance:10uF Tolerance:±10% Tolerance:±10% Voltage Rating:25V Temperature Coefficient:X5R")
      (fields
        (field (name "Manufacturer Part") "CL21A106KAYNNNE")
        (field (name "Manufacturer") "SAMSUNG(三星)")
      )
      (libsource (lib "easyedapro") (part "CL21A106KAYNNNE"))
    )
    (comp (ref "C125")
      (value "10uF")
      (footprint "easyedapro:C0805")
      (description "Capacitance:10uF Tolerance:±10% Tolerance:±10% Voltage Rating:25V Temperature Coefficient:X5R")
      (fields
        (field (name "Manufacturer Part") "CL21A106KAYNNNE")
        (field (name "Manufacturer") "SAMSUNG(三星)")
      )
      (libsource (lib "easyedapro") (part "CL21A106KAYNNNE"))
    )
    (comp (ref "C137")
      (value "100nF")
      (footprint "easyedapro:C0402")
      (description "Capacitance:100nF Tolerance:±10% Tolerance:±10% Voltage Rating:50V Temperature Coefficient:X7R")
      (fields
        (field (name "Manufacturer Part") "CL05B104KB54PNC")
        (field (name "Manufacturer") "SAMSUNG(三星)")
      )
      (libsource (lib "easyedapro") (part "CL05B104KB54PNC"))
    )
    (comp (ref "C138")
      (value "100nF")
      (footprint "easyedapro:C0402")
      (description "Capacitance:100nF Tolerance:±10% Tolerance:±10% Voltage Rating:50V Temperature Coefficient:X7R")
      (fields
        (field (name "Manufacturer Part") "CL05B104KB54PNC")
        (field (name "Manufacturer") "SAMSUNG(三星)")
      )
      (libsource (lib "easyedapro") (part "CL05B104KB54PNC"))
    )
    (comp (ref "D1")
      (value "SMBJ24CA")
      (footprint "easyedapro:SMB_L4.6-W3.6-LS5.3-BI")
      (fields (field (name "Manufacturer") "Brightking(君耀电子)"))
      (libsource (lib "easyedapro") (part "SMBJ24CA_C78416"))
    )
    (comp (ref "J4")
      (value "T34080080-0680")
      (footprint "easyedapro:CONN-TH_T34080080-0680")
      (description "Screw Hole Size:M3 Number of Leg:4")
      (fields (field (name "Manufacturer") "XFCN(兴飞)"))
      (libsource (lib "easyedapro") (part "T34080080-0680"))
    )
    (comp (ref "J5")
      (value "T34080080-0680")
      (footprint "easyedapro:CONN-TH_T34080080-0680")
      (description "Screw Hole Size:M3 Number of Leg:4")
      (fields (field (name "Manufacturer") "XFCN(兴飞)"))
      (libsource (lib "easyedapro") (part "T34080080-0680"))
    )
    (comp (ref "L1")
      (value "12uH")
      (footprint "easyedapro:IND-SMD_L6.0-W6.0_SWPA6045S")
      (fields (field (name "Manufacturer Part") "SWPA6045S120MT") (field (name "Manufacturer") "Sunlord(顺络)"))
      (libsource (lib "easyedapro") (part "SWPA6045S120MT"))
    )
    (comp (ref "L2")
      (value "6.8uH")
      (footprint "easyedapro:IND-SMD_L5.0-W5.0_SWPA5040S")
      (fields
        (field (name "Manufacturer Part") "SWPA5040S6R8MT")
        (field (name "Manufacturer") "Sunlord(顺络)")
        (field (name "Rated Current") "2.5A")
      )
      (libsource (lib "easyedapro") (part "SWPA5040S6R8M"))
    )
    (comp (ref "R31")
      (value "2.7kΩ")
      (footprint "easyedapro:R0603")
      (fields
        (field (name "Manufacturer Part") "0603WAF2701T5E")
        (field (name "Manufacturer") "UNI-ROYAL(厚声)")
      )
      (libsource (lib "easyedapro") (part "0603WAF2701T5E"))
    )
    (comp (ref "R39")
      (value "51kΩ")
      (footprint "easyedapro:R0402")
      (fields
        (field (name "Manufacturer Part") "0402WGF5102TCE")
        (field (name "Manufacturer") "UNI-ROYAL(厚声)")
      )
      (libsource (lib "easyedapro") (part "0402WGF5102TCE"))
    )
    (comp (ref "R80")
      (value "15kΩ")
      (footprint "easyedapro:R0402")
      (fields
        (field (name "Manufacturer Part") "0402WGF1502TCE")
        (field (name "Manufacturer") "UNI-ROYAL(厚声)")
      )
      (libsource (lib "easyedapro") (part "0402WGF1502TCE"))
    )
    (comp (ref "R81")
      (value "3.3kΩ")
      (footprint "easyedapro:R0402")
      (fields
        (field (name "Manufacturer Part") "0402WGF3301TCE")
        (field (name "Manufacturer") "UNI-ROYAL(厚声)")
      )
      (libsource (lib "easyedapro") (part "0402WGF3301TCE"))
    )
    (comp (ref "U12")
      (value "TPS54302DDCT")
      (footprint "easyedapro:TSOT-23-6_L2.9-W1.6-P0.95-LS2.8-BR")
      (fields (field (name "Manufacturer") "TI(德州仪器)"))
      (libsource (lib "easyedapro") (part "TPS54302DDCT"))
    )
    (comp (ref "U29")
      (value "TPS54302DDCT")
      (footprint "easyedapro:TSOT-23-6_L2.9-W1.6-P0.95-LS2.8-BR")
      (fields (field (name "Manufacturer") "TI(德州仪器)"))
      (libsource (lib "easyedapro") (part "TPS54302DDCT"))
    )
    (comp (ref "C4")
      (value "1nF")
      (footprint "easyedapro:C0402")
      (description "Capacitance:1nF Tolerance:±10% Tolerance:±10% Voltage Rating:50V Temperature Coefficient:X7R")
      (fields (field (name "Manufacturer Part") "0402B102K500NT") (field (name "Manufacturer") "FH(风华)"))
      (libsource (lib "easyedapro") (part "0402B102K500NT"))
    )
    (comp (ref "C46")
      (value "10pF")
      (footprint "easyedapro:C0402")
      (description "Capacitance:10pF Tolerance:±5% Tolerance:±5% Voltage Rating:50V Temperature Coefficient:C0G")
      (fields
        (field (name "Manufacturer Part") "CL05C100JB5NNNC")
        (field (name "Manufacturer") "SAMSUNG(三星)")
      )
      (libsource (lib "easyedapro") (part "CL05C100JB5NNNC"))
    )
    (comp (ref "C47")
      (value "10pF")
      (footprint "easyedapro:C0402")
      (description "Capacitance:10pF Tolerance:±5% Tolerance:±5% Voltage Rating:50V Temperature Coefficient:C0G")
      (fields
        (field (name "Manufacturer Part") "CL05C100JB5NNNC")
        (field (name "Manufacturer") "SAMSUNG(三星)")
      )
      (libsource (lib "easyedapro") (part "CL05C100JB5NNNC"))
    )
    (comp (ref "C155")
      (value "100nF")
      (footprint "easyedapro:C0402")
      (description "Capacitance:100nF Tolerance:±10% Tolerance:±10% Voltage Rating:50V Temperature Coefficient:X7R")
      (fields
        (field (name "Manufacturer Part") "CL05B104KB54PNC")
        (field (name "Manufacturer") "SAMSUNG(三星)")
      )
      (libsource (lib "easyedapro") (part "CL05B104KB54PNC"))
    )
    (comp (ref "C156")
      (value "100nF")
      (footprint "easyedapro:C0402")
      (description "Capacitance:100nF Tolerance:±10% Tolerance:±10% Voltage Rating:50V Temperature Coefficient:X7R")
      (fields
        (field (name "Manufacturer Part") "CL05B104KB54PNC")
        (field (name "Manufacturer") "SAMSUNG(三星)")
      )
      (libsource (lib "easyedapro") (part "CL05B104KB54PNC"))
    )
    (comp (ref "C157")
      (value "100nF")
      (footprint "easyedapro:C0402")
      (description "Capacitance:100nF Tolerance:±10% Tolerance:±10% Voltage Rating:50V Temperature Coefficient:X7R")
      (fields
        (field (name "Manufacturer Part") "CL05B104KB54PNC")
        (field (name "Manufacturer") "SAMSUNG(三星)")
      )
      (libsource (lib "easyedapro") (part "CL05B104KB54PNC"))
    )
    (comp (ref "C158")
      (value "100nF")
      (footprint "easyedapro:C0402")
      (description "Capacitance:100nF Tolerance:±10% Tolerance:±10% Voltage Rating:50V Temperature Coefficient:X7R")
      (fields
        (field (name "Manufacturer Part") "CL05B104KB54PNC")
        (field (name "Manufacturer") "SAMSUNG(三星)")
      )
      (libsource (lib "easyedapro") (part "CL05B104KB54PNC"))
    )
    (comp (ref "C159")
      (value "100nF")
      (footprint "easyedapro:C0402")
      (description "Capacitance:100nF Tolerance:±10% Tolerance:±10% Voltage Rating:50V Temperature Coefficient:X7R")
      (fields
        (field (name "Manufacturer Part") "CL05B104KB54PNC")
        (field (name "Manufacturer") "SAMSUNG(三星)")
      )
      (libsource (lib "easyedapro") (part "CL05B104KB54PNC"))
    )
    (comp (ref "C160")
      (value "100nF")
      (footprint "easyedapro:C0402")
      (description "Capacitance:100nF Tolerance:±10% Tolerance:±10% Voltage Rating:50V Temperature Coefficient:X7R")
      (fields
        (field (name "Manufacturer Part") "CL05B104KB54PNC")
        (field (name "Manufacturer") "SAMSUNG(三星)")
      )
      (libsource (lib "easyedapro") (part "CL05B104KB54PNC"))
    )
    (comp (ref "C161")
      (value "100nF")
      (footprint "easyedapro:C0402")
      (description "Capacitance:100nF Tolerance:±10% Tolerance:±10% Voltage Rating:50V Temperature Coefficient:X7R")
      (fields
        (field (name "Manufacturer Part") "CL05B104KB54PNC")
        (field (name "Manufacturer") "SAMSUNG(三星)")
      )
      (libsource (lib "easyedapro") (part "CL05B104KB54PNC"))
    )
    (comp (ref "C162")
      (value "100nF")
      (footprint "easyedapro:C0402")
      (description "Capacitance:100nF Tolerance:±10% Tolerance:±10% Voltage Rating:50V Temperature Coefficient:X7R")
      (fields
        (field (name "Manufacturer Part") "CL05B104KB54PNC")
        (field (name "Manufacturer") "SAMSUNG(三星)")
      )
      (libsource (lib "easyedapro") (part "CL05B104KB54PNC"))
    )
    (comp (ref "C163")
      (value "100nF")
      (footprint "easyedapro:C0402")
      (description "Capacitance:100nF Tolerance:±10% Tolerance:±10% Voltage Rating:50V Temperature Coefficient:X7R")
      (fields
        (field (name "Manufacturer Part") "CL05B104KB54PNC")
        (field (name "Manufacturer") "SAMSUNG(三星)")
      )
      (libsource (lib "easyedapro") (part "CL05B104KB54PNC"))
    )
    (comp (ref "C164")
      (value "100nF")
      (footprint "easyedapro:C0402")
      (description "Capacitance:100nF Tolerance:±10% Tolerance:±10% Voltage Rating:50V Temperature Coefficient:X7R")
      (fields
        (field (name "Manufacturer Part") "CL05B104KB54PNC")
        (field (name "Manufacturer") "SAMSUNG(三星)")
      )
      (libsource (lib "easyedapro") (part "CL05B104KB54PNC"))
    )
    (comp (ref "J6")
      (value "B3B-XH-AM-BK(LF)(SN)")
      (footprint "easyedapro:CONN-TH_B3B-XH-AM-BK-LF-SN")
      (fields (field (name "Manufacturer") "JST"))
      (libsource (lib "easyedapro") (part "B3B-XH-AM-BK(LF)(SN)"))
    )
    (comp (ref "J7")
      (value "B3B-XH-AM-BK(LF)(SN)")
      (footprint "easyedapro:CONN-TH_B3B-XH-AM-BK-LF-SN")
      (fields (field (name "Manufacturer") "JST"))
      (libsource (lib "easyedapro") (part "B3B-XH-AM-BK(LF)(SN)"))
    )
    (comp (ref "J8")
      (value "PH2.54-1X5P-H25")
      (footprint "easyedapro:HDR-TH_5P-P2.54-V-M-3")
      (fields (field (name "Manufacturer") "JXTCONN(聚兴泰)"))
      (libsource (lib "easyedapro") (part "PH2.54-1X5P-H25"))
    )
    (comp (ref "J9")
      (value "PH2.54-06PB2G-H25")
      (footprint "easyedapro:HDR-TH_6P-P2.54-V-M_BLUE")
      (fields (field (name "Manufacturer") "JXTCONN(聚兴泰)"))
      (libsource (lib "easyedapro") (part "PH2.54-06PB2G-H25"))
    )
    (comp (ref "LED1")
      (value "KT-0603R")
      (footprint "easyedapro:LED0603-RD")
      (fields (field (name "Manufacturer") "KENTO"))
      (libsource (lib "easyedapro") (part "KT-0603R"))
    )
    (comp (ref "LED2")
      (value "KT-0603R")
      (footprint "easyedapro:LED0603-RD")
      (fields (field (name "Manufacturer") "KENTO"))
      (libsource (lib "easyedapro") (part "KT-0603R"))
    )
    (comp (ref "LED3")
      (value "KT-0603R")
      (footprint "easyedapro:LED0603-RD")
      (fields (field (name "Manufacturer") "KENTO"))
      (libsource (lib "easyedapro") (part "KT-0603R"))
    )
    (comp (ref "LED4")
      (value "KT-0603R")
      (footprint "easyedapro:LED0603-RD")
      (fields (field (name "Manufacturer") "KENTO"))
      (libsource (lib "easyedapro") (part "KT-0603R"))
    )
    (comp (ref "LED5")
      (value "KT-0603R")
      (footprint "easyedapro:LED0603-RD")
      (fields (field (name "Manufacturer") "KENTO"))
      (libsource (lib "easyedapro") (part "KT-0603R"))
    )
    (comp (ref "LED6")
      (value "KT-0603R")
      (footprint "easyedapro:LED0603-RD")
      (fields (field (name "Manufacturer") "KENTO"))
      (libsource (lib "easyedapro") (part "KT-0603R"))
    )
    (comp (ref "LED7")
      (value "KT-0603R")
      (footprint "easyedapro:LED0603-RD")
      (fields (field (name "Manufacturer") "KENTO"))
      (libsource (lib "easyedapro") (part "KT-0603R"))
    )
    (comp (ref "LED8")
      (value "KT-0603R")
      (footprint "easyedapro:LED0603-RD")
      (fields (field (name "Manufacturer") "KENTO"))
      (libsource (lib "easyedapro") (part "KT-0603R"))
    )
    (comp (ref "LED9")
      (value "KT-0603R")
      (footprint "easyedapro:LED0603-RD")
      (fields (field (name "Manufacturer") "KENTO"))
      (libsource (lib "easyedapro") (part "KT-0603R"))
    )
    (comp (ref "LED10")
      (value "KT-0603R")
      (footprint "easyedapro:LED0603-RD")
      (fields (field (name "Manufacturer") "KENTO"))
      (libsource (lib "easyedapro") (part "KT-0603R"))
    )
    (comp (ref "LED11")
      (value "KT-0603R")
      (footprint "easyedapro:LED0603-RD")
      (fields (field (name "Manufacturer") "KENTO"))
      (libsource (lib "easyedapro") (part "KT-0603R"))
    )
    (comp (ref "LED12")
      (value "KT-0603R")
      (footprint "easyedapro:LED0603-RD")
      (fields (field (name "Manufacturer") "KENTO"))
      (libsource (lib "easyedapro") (part "KT-0603R"))
    )
    (comp (ref "LED13")
      (value "KT-0603R")
      (footprint "easyedapro:LED0603-RD")
      (fields (field (name "Manufacturer") "KENTO"))
      (libsource (lib "easyedapro") (part "KT-0603R"))
    )
    (comp (ref "LED14")
      (value "KT-0603R")
      (footprint "easyedapro:LED0603-RD")
      (fields (field (name "Manufacturer") "KENTO"))
      (libsource (lib "easyedapro") (part "KT-0603R"))
    )
    (comp (ref "LED15")
      (value "KT-0603R")
      (footprint "easyedapro:LED0603-RD")
      (fields (field (name "Manufacturer") "KENTO"))
      (libsource (lib "easyedapro") (part "KT-0603R"))
    )
    (comp (ref "LED16")
      (value "KT-0603R")
      (footprint "easyedapro:LED0603-RD")
      (fields (field (name "Manufacturer") "KENTO"))
      (libsource (lib "easyedapro") (part "KT-0603R"))
    )
    (comp (ref "LED17")
      (value "KT-0603R")
      (footprint "easyedapro:LED0603-RD")
      (fields (field (name "Manufacturer") "KENTO"))
      (libsource (lib "easyedapro") (part "KT-0603R"))
    )
    (comp (ref "LED18")
      (value "KT-0603R")
      (footprint "easyedapro:LED0603-RD")
      (fields (field (name "Manufacturer") "KENTO"))
      (libsource (lib "easyedapro") (part "KT-0603R"))
    )
    (comp (ref "R99")
      (value "15kΩ")
      (footprint "easyedapro:R0402")
      (fields
        (field (name "Manufacturer Part") "0402WGF1502TCE")
        (field (name "Manufacturer") "UNI-ROYAL(厚声)")
      )
      (libsource (lib "easyedapro") (part "0402WGF1502TCE"))
    )
    (comp (ref "R100")
      (value "15kΩ")
      (footprint "easyedapro:R0402")
      (fields
        (field (name "Manufacturer Part") "0402WGF1502TCE")
        (field (name "Manufacturer") "UNI-ROYAL(厚声)")
      )
      (libsource (lib "easyedapro") (part "0402WGF1502TCE"))
    )
    (comp (ref "R101")
      (value "15kΩ")
      (footprint "easyedapro:R0402")
      (fields
        (field (name "Manufacturer Part") "0402WGF1502TCE")
        (field (name "Manufacturer") "UNI-ROYAL(厚声)")
      )
      (libsource (lib "easyedapro") (part "0402WGF1502TCE"))
    )
    (comp (ref "R102")
      (value "3.3kΩ")
      (footprint "easyedapro:R0402")
      (fields
        (field (name "Manufacturer Part") "0402WGF3301TCE")
        (field (name "Manufacturer") "UNI-ROYAL(厚声)")
      )
      (libsource (lib "easyedapro") (part "0402WGF3301TCE"))
    )
    (comp (ref "R103")
      (value "3.3kΩ")
      (footprint "easyedapro:R0402")
      (fields
        (field (name "Manufacturer Part") "0402WGF3301TCE")
        (field (name "Manufacturer") "UNI-ROYAL(厚声)")
      )
      (libsource (lib "easyedapro") (part "0402WGF3301TCE"))
    )
    (comp (ref "R104")
      (value "3.3kΩ")
      (footprint "easyedapro:R0402")
      (fields
        (field (name "Manufacturer Part") "0402WGF3301TCE")
        (field (name "Manufacturer") "UNI-ROYAL(厚声)")
      )
      (libsource (lib "easyedapro") (part "0402WGF3301TCE"))
    )
    (comp (ref "R105")
      (value "3.3kΩ")
      (footprint "easyedapro:R0402")
      (fields
        (field (name "Manufacturer Part") "0402WGF3301TCE")
        (field (name "Manufacturer") "UNI-ROYAL(厚声)")
      )
      (libsource (lib "easyedapro") (part "0402WGF3301TCE"))
    )
    (comp (ref "R106")
      (value "3.3kΩ")
      (footprint "easyedapro:R0402")
      (fields
        (field (name "Manufacturer Part") "0402WGF3301TCE")
        (field (name "Manufacturer") "UNI-ROYAL(厚声)")
      )
      (libsource (lib "easyedapro") (part "0402WGF3301TCE"))
    )
    (comp (ref "R107")
      (value "3.3kΩ")
      (footprint "easyedapro:R0402")
      (fields
        (field (name "Manufacturer Part") "0402WGF3301TCE")
        (field (name "Manufacturer") "UNI-ROYAL(厚声)")
      )
      (libsource (lib "easyedapro") (part "0402WGF3301TCE"))
    )
    (comp (ref "R108")
      (value "3.3kΩ")
      (footprint "easyedapro:R0402")
      (fields
        (field (name "Manufacturer Part") "0402WGF3301TCE")
        (field (name "Manufacturer") "UNI-ROYAL(厚声)")
      )
      (libsource (lib "easyedapro") (part "0402WGF3301TCE"))
    )
    (comp (ref "R109")
      (value "3.3kΩ")
      (footprint "easyedapro:R0402")
      (fields
        (field (name "Manufacturer Part") "0402WGF3301TCE")
        (field (name "Manufacturer") "UNI-ROYAL(厚声)")
      )
      (libsource (lib "easyedapro") (part "0402WGF3301TCE"))
    )
    (comp (ref "R110")
      (value "3.3kΩ")
      (footprint "easyedapro:R0402")
      (fields
        (field (name "Manufacturer Part") "0402WGF3301TCE")
        (field (name "Manufacturer") "UNI-ROYAL(厚声)")
      )
      (libsource (lib "easyedapro") (part "0402WGF3301TCE"))
    )
    (comp (ref "R111")
      (value "3.3kΩ")
      (footprint "easyedapro:R0402")
      (fields
        (field (name "Manufacturer Part") "0402WGF3301TCE")
        (field (name "Manufacturer") "UNI-ROYAL(厚声)")
      )
      (libsource (lib "easyedapro") (part "0402WGF3301TCE"))
    )
    (comp (ref "R112")
      (value "3.3kΩ")
      (footprint "easyedapro:R0402")
      (fields
        (field (name "Manufacturer Part") "0402WGF3301TCE")
        (field (name "Manufacturer") "UNI-ROYAL(厚声)")
      )
      (libsource (lib "easyedapro") (part "0402WGF3301TCE"))
    )
    (comp (ref "R113")
      (value "3.3kΩ")
      (footprint "easyedapro:R0402")
      (fields
        (field (name "Manufacturer Part") "0402WGF3301TCE")
        (field (name "Manufacturer") "UNI-ROYAL(厚声)")
      )
      (libsource (lib "easyedapro") (part "0402WGF3301TCE"))
    )
    (comp (ref "R114")
      (value "3.3kΩ")
      (footprint "easyedapro:R0402")
      (fields
        (field (name "Manufacturer Part") "0402WGF3301TCE")
        (field (name "Manufacturer") "UNI-ROYAL(厚声)")
      )
      (libsource (lib "easyedapro") (part "0402WGF3301TCE"))
    )
    (comp (ref "R115")
      (value "3.3kΩ")
      (footprint "easyedapro:R0402")
      (fields
        (field (name "Manufacturer Part") "0402WGF3301TCE")
        (field (name "Manufacturer") "UNI-ROYAL(厚声)")
      )
      (libsource (lib "easyedapro") (part "0402WGF3301TCE"))
    )
    (comp (ref "R116")
      (value "15kΩ")
      (footprint "easyedapro:R0402")
      (fields
        (field (name "Manufacturer Part") "0402WGF1502TCE")
        (field (name "Manufacturer") "UNI-ROYAL(厚声)")
      )
      (libsource (lib "easyedapro") (part "0402WGF1502TCE"))
    )
    (comp (ref "R117")
      (value "3.3kΩ")
      (footprint "easyedapro:R0402")
      (fields
        (field (name "Manufacturer Part") "0402WGF3301TCE")
        (field (name "Manufacturer") "UNI-ROYAL(厚声)")
      )
      (libsource (lib "easyedapro") (part "0402WGF3301TCE"))
    )
    (comp (ref "R118")
      (value "3.3kΩ")
      (footprint "easyedapro:R0402")
      (fields
        (field (name "Manufacturer Part") "0402WGF3301TCE")
        (field (name "Manufacturer") "UNI-ROYAL(厚声)")
      )
      (libsource (lib "easyedapro") (part "0402WGF3301TCE"))
    )
    (comp (ref "R119")
      (value "3.3kΩ")
      (footprint "easyedapro:R0402")
      (fields
        (field (name "Manufacturer Part") "0402WGF3301TCE")
        (field (name "Manufacturer") "UNI-ROYAL(厚声)")
      )
      (libsource (lib "easyedapro") (part "0402WGF3301TCE"))
    )
    (comp (ref "R120")
      (value "3.3kΩ")
      (footprint "easyedapro:R0402")
      (fields
        (field (name "Manufacturer Part") "0402WGF3301TCE")
        (field (name "Manufacturer") "UNI-ROYAL(厚声)")
      )
      (libsource (lib "easyedapro") (part "0402WGF3301TCE"))
    )
    (comp (ref "R121")
      (value "3.3kΩ")
      (footprint "easyedapro:R0402")
      (fields
        (field (name "Manufacturer Part") "0402WGF3301TCE")
        (field (name "Manufacturer") "UNI-ROYAL(厚声)")
      )
      (libsource (lib "easyedapro") (part "0402WGF3301TCE"))
    )
    (comp (ref "R122")
      (value "3.3kΩ")
      (footprint "easyedapro:R0402")
      (fields
        (field (name "Manufacturer Part") "0402WGF3301TCE")
        (field (name "Manufacturer") "UNI-ROYAL(厚声)")
      )
      (libsource (lib "easyedapro") (part "0402WGF3301TCE"))
    )
    (comp (ref "R123")
      (value "3.3kΩ")
      (footprint "easyedapro:R0402")
      (fields
        (field (name "Manufacturer Part") "0402WGF3301TCE")
        (field (name "Manufacturer") "UNI-ROYAL(厚声)")
      )
      (libsource (lib "easyedapro") (part "0402WGF3301TCE"))
    )
    (comp (ref "R124")
      (value "3.3kΩ")
      (footprint "easyedapro:R0402")
      (fields
        (field (name "Manufacturer Part") "0402WGF3301TCE")
        (field (name "Manufacturer") "UNI-ROYAL(厚声)")
      )
      (libsource (lib "easyedapro") (part "0402WGF3301TCE"))
    )
    (comp (ref "R125")
      (value "3.3kΩ")
      (footprint "easyedapro:R0402")
      (fields
        (field (name "Manufacturer Part") "0402WGF3301TCE")
        (field (name "Manufacturer") "UNI-ROYAL(厚声)")
      )
      (libsource (lib "easyedapro") (part "0402WGF3301TCE"))
    )
    (comp (ref "R126")
      (value "3.3kΩ")
      (footprint "easyedapro:R0402")
      (fields
        (field (name "Manufacturer Part") "0402WGF3301TCE")
        (field (name "Manufacturer") "UNI-ROYAL(厚声)")
      )
      (libsource (lib "easyedapro") (part "0402WGF3301TCE"))
    )
    (comp (ref "U5")
      (value "AS5600-ASOM")
      (footprint "easyedapro:SOIC-8_L5.0-W4.0-P1.27-LS6.0-BL")
      (description "Supply Voltage:5V；3.3V Supply Voltage:5V；3.3V Rotation Angle:0°~360° Rotation Angle:0°~360°")
      (fields (field (name "Manufacturer") "ams(艾迈斯半导体)"))
      (libsource (lib "easyedapro") (part "AS5600-ASOM"))
    )
    (comp (ref "U6")
      (value "SP3485EN-L/TR")
      (footprint "easyedapro:SOIC-8_L5.0-W4.0-P1.27-LS6.0-BL")
      (fields (field (name "Manufacturer") "MaxLinear(迈凌)"))
      (libsource (lib "easyedapro") (part "SP3485EN-L/TR"))
    )
    (comp (ref "U7")
      (value "SP3485EN-L/TR")
      (footprint "easyedapro:SOIC-8_L5.0-W4.0-P1.27-LS6.0-BL")
      (fields (field (name "Manufacturer") "MaxLinear(迈凌)"))
      (libsource (lib "easyedapro") (part "SP3485EN-L/TR"))
    )
    (comp (ref "U15")
      (value "STM32G474RBT6")
      (footprint "easyedapro:LQFP-64_L10.0-W10.0-P0.50-LS12.0-BL")
      (fields (field (name "Manufacturer") "ST(意法半导体)"))
      (libsource (lib "easyedapro") (part "STM32G474RBT6"))
    )
    (comp (ref "U16")
      (value "M24C64-RMN6TP")
      (footprint "easyedapro:SOIC-8_L5.0-W4.0-P1.27-LS6.0-BL")
      (fields (field (name "Manufacturer") "ST(意法半导体)"))
      (libsource (lib "easyedapro") (part "M24C64-RMN6TP"))
    )
    (comp (ref "X1")
      (value "25MHz")
      (footprint "easyedapro:CRYSTAL-SMD_4P-L3.2-W2.5-BL")
      (fields (field (name "Manufacturer Part") "X322525MOB4SI") (field (name "Manufacturer") "YXC(扬兴晶振)"))
      (libsource (lib "easyedapro") (part "X322525MOB4SI"))
    )
  )
  (nets
    (net (code "1") (name "1_485_A") (class "Default")
      (node (ref "J6") (pin "2") (pinfunction "2_2") (pintype "unspecified"))
      (node (ref "U6") (pin "6") (pinfunction "A_6") (pintype "unspecified"))
    )
    (net (code "2") (name "1_485_B") (class "Default")
      (node (ref "J6") (pin "1") (pinfunction "1_1") (pintype "unspecified"))
      (node (ref "U6") (pin "7") (pinfunction "B_7") (pintype "unspecified"))
    )
    (net (code "3") (name "2_485_A") (class "Default")
      (node (ref "J7") (pin "2") (pinfunction "2_2") (pintype "unspecified"))
      (node (ref "U7") (pin "6") (pinfunction "A_6") (pintype "unspecified"))
    )
    (net (code "4") (name "2_485_B") (class "Default")
      (node (ref "J7") (pin "1") (pinfunction "1_1") (pintype "unspecified"))
      (node (ref "U7") (pin "7") (pinfunction "B_7") (pintype "unspecified"))
    )
    (net (code "5") (name "3V3") (class "Default")
      (node (ref "C107") (pin "2") (pinfunction "2_2") (pintype "input"))
      (node (ref "C146") (pin "2") (pinfunction "2_2") (pintype "input"))
      (node (ref "C147") (pin "2") (pinfunction "2_2") (pintype "input"))
      (node (ref "C152") (pin "2") (pinfunction "2_2") (pintype "input"))
      (node (ref "C155") (pin "2") (pinfunction "2_2") (pintype "input"))
      (node (ref "C156") (pin "2") (pinfunction "2_2") (pintype "input"))
      (node (ref "C157") (pin "2") (pinfunction "2_2") (pintype "input"))
      (node (ref "C158") (pin "2") (pinfunction "2_2") (pintype "input"))
      (node (ref "C159") (pin "2") (pinfunction "2_2") (pintype "input"))
      (node (ref "C160") (pin "2") (pinfunction "2_2") (pintype "input"))
      (node (ref "C161") (pin "2") (pinfunction "2_2") (pintype "input"))
      (node (ref "C162") (pin "2") (pinfunction "2_2") (pintype "input"))
      (node (ref "C163") (pin "2") (pinfunction "2_2") (pintype "input"))
      (node (ref "C54") (pin "2") (pinfunction "2_2") (pintype "input"))
      (node (ref "C55") (pin "2") (pinfunction "2_2") (pintype "input"))
      (node (ref "J8") (pin "5") (pinfunction "5_5") (pintype "unspecified"))
      (node (ref "L2") (pin "2") (pinfunction "2_2") (pintype "input"))
      (node (ref "LED10") (pin "2") (pinfunction "A_2") (pintype "unspecified"))
      (node (ref "LED11") (pin "2") (pinfunction "A_2") (pintype "unspecified"))
      (node (ref "LED12") (pin "2") (pinfunction "A_2") (pintype "unspecified"))
      (node (ref "LED13") (pin "2") (pinfunction "A_2") (pintype "unspecified"))
      (node (ref "LED14") (pin "2") (pinfunction "A_2") (pintype "unspecified"))
      (node (ref "LED9") (pin "2") (pinfunction "A_2") (pintype "unspecified"))
      (node (ref "R102") (pin "2") (pinfunction "2_2") (pintype "input"))
      (node (ref "R103") (pin "2") (pinfunction "2_2") (pintype "input"))
      (node (ref "R104") (pin "2") (pinfunction "2_2") (pintype "input"))
      (node (ref "R105") (pin "2") (pinfunction "2_2") (pintype "input"))
      (node (ref "R116") (pin "2") (pinfunction "2_2") (pintype "input"))
      (node (ref "R80") (pin "2") (pinfunction "2_2") (pintype "input"))
      (node (ref "R82") (pin "2") (pinfunction "2_2") (pintype "input"))
      (node (ref "R83") (pin "2") (pinfunction "2_2") (pintype "input"))
      (node (ref "R84") (pin "2") (pinfunction "2_2") (pintype "input"))
      (node (ref "R99") (pin "2") (pinfunction "2_2") (pintype "input"))
      (node (ref "U15") (pin "1") (pinfunction "VBAT_1") (pintype "unspecified"))
      (node (ref "U15") (pin "16") (pinfunction "VDD_16") (pintype "unspecified"))
      (node (ref "U15") (pin "28") (pinfunction "VREF+_28") (pintype "unspecified"))
      (node (ref "U15") (pin "29") (pinfunction "VDDA_29") (pintype "unspecified"))
      (node (ref "U15") (pin "32") (pinfunction "VDD_32") (pintype "unspecified"))
      (node (ref "U15") (pin "48") (pinfunction "VDD_48") (pintype "unspecified"))
      (node (ref "U15") (pin "64") (pinfunction "VDD_64") (pintype "unspecified"))
      (node (ref "U16") (pin "8") (pinfunction "VCC_8") (pintype "unspecified"))
      (node (ref "U2") (pin "5") (pinfunction "V+_5") (pintype "unspecified"))
      (node (ref "U23") (pin "5") (pinfunction "V+_5") (pintype "unspecified"))
      (node (ref "U26") (pin "5") (pinfunction "V+_5") (pintype "unspecified"))
      (node (ref "U5") (pin "1") (pinfunction "VDD5V_1") (pintype "unspecified"))
      (node (ref "U5") (pin "2") (pinfunction "VDD3V3_2") (pintype "unspecified"))
      (node (ref "U5") (pin "5") (pinfunction "PGO_5") (pintype "unspecified"))
      (node (ref "U6") (pin "8") (pinfunction "VCC_8") (pintype "unspecified"))
      (node (ref "U7") (pin "8") (pinfunction "VCC_8") (pintype "unspecified"))
    )
    (net (code "6") (name "12V") (class "Default")
      (node (ref "C109") (pin "2") (pinfunction "2_2") (pintype "input"))
      (node (ref "C118") (pin "2") (pinfunction "2_2") (pintype "unspecified"))
      (node (ref "C119") (pin "2") (pinfunction "2_2") (pintype "unspecified"))
      (node (ref "C120") (pin "2") (pinfunction "2_2") (pintype "unspecified"))
      (node (ref "C121") (pin "2") (pinfunction "2_2") (pintype "unspecified"))
      (node (ref "C122") (pin "2") (pinfunction "2_2") (pintype "unspecified"))
      (node (ref "C123") (pin "2") (pinfunction "2_2") (pintype "unspecified"))
      (node (ref "C124") (pin "2") (pinfunction "2_2") (pintype "unspecified"))
      (node (ref "C125") (pin "2") (pinfunction "2_2") (pintype "unspecified"))
      (node (ref "C139") (pin "2") (pinfunction "2_2") (pintype "input"))
      (node (ref "C144") (pin "2") (pinfunction "2_2") (pintype "input"))
      (node (ref "C148") (pin "2") (pinfunction "2_2") (pintype "input"))
      (node (ref "C153") (pin "2") (pinfunction "2_2") (pintype "input"))
      (node (ref "D3") (pin "2") (pinfunction "A_2") (pintype "unspecified"))
      (node (ref "D4") (pin "2") (pinfunction "A_2") (pintype "unspecified"))
      (node (ref "D5") (pin "2") (pinfunction "A_2") (pintype "unspecified"))
      (node (ref "D6") (pin "2") (pinfunction "A_2") (pintype "unspecified"))
      (node (ref "L1") (pin "2") (pinfunction "2_2") (pintype "unspecified"))
      (node (ref "R39") (pin "2") (pinfunction "2_2") (pintype "input"))
      (node (ref "U20") (pin "1") (pinfunction "VCC_1") (pintype "unspecified"))
      (node (ref "U22") (pin "1") (pinfunction "VCC_1") (pintype "unspecified"))
      (node (ref "U25") (pin "1") (pinfunction "VCC_1") (pintype "unspecified"))
      (node (ref "U28") (pin "1") (pinfunction "VCC_1") (pintype "unspecified"))
    )
    (net (code "7") (name "24V") (class "Default")
      (node (ref "C100") (pin "2") (pinfunction "2_2") (pintype "input"))
      (node (ref "C110") (pin "1") (pinfunction "1_1") (pintype "input"))
      (node (ref "C111") (pin "1") (pinfunction "1_1") (pintype "input"))
      (node (ref "C112") (pin "1") (pinfunction "1_1") (pintype "input"))
      (node (ref "C113") (pin "1") (pinfunction "1_1") (pintype "input"))
      (node (ref "C9") (pin "2") (pinfunction "2_2") (pintype "input"))
      (node (ref "C96") (pin "2") (pinfunction "2_2") (pintype "input"))
      (node (ref "C97") (pin "2") (pinfunction "2_2") (pintype "input"))
      (node (ref "C98") (pin "2") (pinfunction "2_2") (pintype "input"))
      (node (ref "D1") (pin "1") (pinfunction "K_1") (pintype "unspecified"))
      (node (ref "D7") (pin "1") (pinfunction "K_1") (pintype "unspecified"))
      (node (ref "J4") (pin "1") (pinfunction "1_1") (pintype "unspecified"))
      (node (ref "J4") (pin "2") (pinfunction "2_2") (pintype "unspecified"))
      (node (ref "J4") (pin "3") (pinfunction "3_3") (pintype "unspecified"))
      (node (ref "J4") (pin "4") (pinfunction "4_4") (pintype "unspecified"))
      (node (ref "Q1") (pin "2") (pinfunction "D_2") (pintype "unspecified"))
      (node (ref "Q7") (pin "2") (pinfunction "D_2") (pintype "unspecified"))
      (node (ref "Q9") (pin "2") (pinfunction "D_2") (pintype "unspecified"))
      (node (ref "R69") (pin "2") (pinfunction "2_2") (pintype "unspecified"))
      (node (ref "R70") (pin "2") (pinfunction "2_2") (pintype "unspecified"))
      (node (ref "R92") (pin "2") (pinfunction "2_2") (pintype "input"))
      (node (ref "U12") (pin "3") (pinfunction "VIN_3") (pintype "unspecified"))
      (node (ref "U29") (pin "3") (pinfunction "VIN_3") (pintype "unspecified"))
    )
    (net (code "8") (name "CURR_A") (class "Default")
      (node (ref "C43") (pin "2") (pinfunction "2_2") (pintype "input"))
      (node (ref "R94") (pin "1") (pinfunction "1_1") (pintype "input"))
      (node (ref "U15") (pin "12") (pinfunction "PA0_12") (pintype "unspecified"))
    )
    (net (code "9") (name "CURR_B") (class "Default")
      (node (ref "C116") (pin "2") (pinfunction "2_2") (pintype "input"))
      (node (ref "R95") (pin "1") (pinfunction "1_1") (pintype "input"))
      (node (ref "U15") (pin "13") (pinfunction "PA1_13") (pintype "unspecified"))
    )
    (net (code "10") (name "CURR_C") (class "Default")
      (node (ref "C117") (pin "2") (pinfunction "2_2") (pintype "input"))
      (node (ref "R96") (pin "1") (pinfunction "1_1") (pintype "input"))
      (node (ref "U15") (pin "14") (pinfunction "PA2_14") (pintype "unspecified"))
    )
    (net (code "11") (name "DEBUG_RX") (class "Default")
      (node (ref "J9") (pin "3") (pinfunction "3_3") (pintype "unspecified"))
      (node (ref "R116") (pin "1") (pinfunction "1_1") (pintype "input"))
      (node (ref "R121") (pin "1") (pinfunction "1_1") (pintype "input"))
      (node (ref "U15") (pin "53") (pinfunction "PC11_53") (pintype "unspecified"))
    )
    (net (code "12") (name "DEBUG_TX") (class "Default")
      (node (ref "J9") (pin "4") (pinfunction "4_4") (pintype "unspecified"))
      (node (ref "R122") (pin "1") (pinfunction "1_1") (pintype "input"))
      (node (ref "U15") (pin "52") (pinfunction "PC10_52") (pintype "unspecified"))
    )
    (net (code "13") (name "GND") (class "Default")
      (node (ref "C100") (pin "1") (pinfunction "1_1") (pintype "input"))
      (node (ref "C107") (pin "1") (pinfunction "1_1") (pintype "input"))
      (node (ref "C110") (pin "2") (pinfunction "2_2") (pintype "input"))
      (node (ref "C111") (pin "2") (pinfunction "2_2") (pintype "input"))
      (node (ref "C112") (pin "2") (pinfunction "2_2") (pintype "input"))
      (node (ref "C113") (pin "2") (pinfunction "2_2") (pintype "input"))
      (node (ref "C116") (pin "1") (pinfunction "1_1") (pintype "input"))
      (node (ref "C117") (pin "1") (pinfunction "1_1") (pintype "input"))
      (node (ref "C118") (pin "1") (pinfunction "1_1") (pintype "unspecified"))
      (node (ref "C119") (pin "1") (pinfunction "1_1") (pintype "unspecified"))
      (node (ref "C120") (pin "1") (pinfunction "1_1") (pintype "unspecified"))
      (node (ref "C121") (pin "1") (pinfunction "1_1") (pintype "unspecified"))
      (node (ref "C122") (pin "1") (pinfunction "1_1") (pintype "unspecified"))
      (node (ref "C123") (pin "1") (pinfunction "1_1") (pintype "unspecified"))
      (node (ref "C124") (pin "1") (pinfunction "1_1") (pintype "unspecified"))
      (node (ref "C125") (pin "1") (pinfunction "1_1") (pintype "unspecified"))
      (node (ref "C126") (pin "1") (pinfunction "1_1") (pintype "input"))
      (node (ref "C139") (pin "1") (pinfunction "1_1") (pintype "input"))
      (node (ref "C144") (pin "1") (pinfunction "1_1") (pintype "input"))
      (node (ref "C146") (pin "1") (pinfunction "1_1") (pintype "input"))
      (node (ref "C147") (pin "1") (pinfunction "1_1") (pintype "input"))
      (node (ref "C148") (pin "1") (pinfunction "1_1") (pintype "input"))
      (node (ref "C152") (pin "1") (pinfunction "1_1") (pintype "input"))
      (node (ref "C153") (pin "1") (pinfunction "1_1") (pintype "input"))
      (node (ref "C155") (pin "1") (pinfunction "1_1") (pintype "input"))
      (node (ref "C156") (pin "1") (pinfunction "1_1") (pintype "input"))
      (node (ref "C157") (pin "1") (pinfunction "1_1") (pintype "input"))
      (node (ref "C158") (pin "1") (pinfunction "1_1") (pintype "input"))
      (node (ref "C159") (pin "1") (pinfunction "1_1") (pintype "input"))
      (node (ref "C160") (pin "1") (pinfunction "1_1") (pintype "input"))
      (node (ref "C161") (pin "1") (pinfunction "1_1") (pintype "input"))
      (node (ref "C162") (pin "1") (pinfunction "1_1") (pintype "input"))
      (node (ref "C163") (pin "1") (pinfunction "1_1") (pintype "input"))
      (node (ref "C164") (pin "1") (pinfunction "1_1") (pintype "input"))
      (node (ref "C4") (pin "1") (pinfunction "1_1") (pintype "input"))
      (node (ref "C43") (pin "1") (pinfunction "1_1") (pintype "input"))
      (node (ref "C46") (pin "1") (pinfunction "1_1") (pintype "unspecified"))
      (node (ref "C47") (pin "1") (pinfunction "1_1") (pintype "unspecified"))
      (node (ref "C55") (pin "1") (pinfunction "1_1") (pintype "input"))
      (node (ref "C9") (pin "1") (pinfunction "1_1") (pintype "input"))
      (node (ref "C96") (pin "1") (pinfunction "1_1") (pintype "input"))
      (node (ref "C97") (pin "1") (pinfunction "1_1") (pintype "input"))
      (node (ref "C98") (pin "1") (pinfunction "1_1") (pintype "input"))
      (node (ref "D1") (pin "2") (pinfunction "A_2") (pintype "unspecified"))
      (node (ref "J5") (pin "1") (pinfunction "1_1") (pintype "unspecified"))
      (node (ref "J5") (pin "2") (pinfunction "2_2") (pintype "unspecified"))
      (node (ref "J5") (pin "3") (pinfunction "3_3") (pintype "unspecified"))
      (node (ref "J5") (pin "4") (pinfunction "4_4") (pintype "unspecified"))
      (node (ref "J6") (pin "3") (pinfunction "3_3") (pintype "unspecified"))
      (node (ref "J7") (pin "3") (pinfunction "3_3") (pintype "unspecified"))
      (node (ref "J8") (pin "1") (pinfunction "1_1") (pintype "unspecified"))
      (node (ref "J9") (pin "2") (pinfunction "2_2") (pintype "unspecified"))
      (node (ref "LED1") (pin "1") (pinfunction "K_1") (pintype "unspecified"))
      (node (ref "LED15") (pin "1") (pinfunction "K_1") (pintype "unspecified"))
      (node (ref "LED16") (pin "1") (pinfunction "K_1") (pintype "unspecified"))
      (node (ref "LED17") (pin "1") (pinfunction "K_1") (pintype "unspecified"))
      (node (ref "LED18") (pin "1") (pinfunction "K_1") (pintype "unspecified"))
      (node (ref "LED2") (pin "1") (pinfunction "K_1") (pintype "unspecified"))
      (node (ref "LED3") (pin "1") (pinfunction "K_1") (pintype "unspecified"))
      (node (ref "LED4") (pin "1") (pinfunction "K_1") (pintype "unspecified"))
      (node (ref "LED5") (pin "1") (pinfunction "K_1") (pintype "unspecified"))
      (node (ref "LED6") (pin "1") (pinfunction "K_1") (pintype "unspecified"))
      (node (ref "LED7") (pin "1") (pinfunction "K_1") (pintype "unspecified"))
      (node (ref "LED8") (pin "1") (pinfunction "K_1") (pintype "unspecified"))
      (node (ref "Q12") (pin "3") (pinfunction "S_3") (pintype "unspecified"))
      (node (ref "R1") (pin "1") (pinfunction "1_1") (pintype "unspecified"))
      (node (ref "R100") (pin "1") (pinfunction "1_1") (pintype "input"))
      (node (ref "R101") (pin "1") (pinfunction "1_1") (pintype "input"))
      (node (ref "R106") (pin "1") (pinfunction "1_1") (pintype "input"))
      (node (ref "R31") (pin "1") (pinfunction "1_1") (pintype "input"))
      (node (ref "R45") (pin "2") (pinfunction "2_2") (pintype "input"))
      (node (ref "R47") (pin "1") (pinfunction "1_1") (pintype "unspecified"))
      (node (ref "R52") (pin "2") (pinfunction "2_2") (pintype "input"))
      (node (ref "R54") (pin "1") (pinfunction "1_1") (pintype "unspecified"))
      (node (ref "R6") (pin "2") (pinfunction "2_2") (pintype "input"))
      (node (ref "R81") (pin "1") (pinfunction "1_1") (pintype "input"))
      (node (ref "R86") (pin "2") (pinfunction "2_2") (pintype "input"))
      (node (ref "R88") (pin "2") (pinfunction "2_2") (pintype "input"))
      (node (ref "R90") (pin "2") (pinfunction "2_2") (pintype "input"))
      (node (ref "R93") (pin "1") (pinfunction "1_1") (pintype "input"))
      (node (ref "R97") (pin "2") (pinfunction "2_2") (pintype "input"))
      (node (ref "U12") (pin "1") (pinfunction "GND_1") (pintype "unspecified"))
      (node (ref "U15") (pin "15") (pinfunction "VSS_15") (pintype "unspecified"))
      (node (ref "U15") (pin "27") (pinfunction "VSSA_27") (pintype "unspecified"))
      (node (ref "U15") (pin "31") (pinfunction "VSS_31") (pintype "unspecified"))
      (node (ref "U15") (pin "47") (pinfunction "VSS_47") (pintype "unspecified"))
      (node (ref "U15") (pin "63") (pinfunction "VSS_63") (pintype "unspecified"))
      (node (ref "U16") (pin "1") (pinfunction "A0_1") (pintype "unspecified"))
      (node (ref "U16") (pin "2") (pinfunction "A1_2") (pintype "unspecified"))
      (node (ref "U16") (pin "3") (pinfunction "A2_3") (pintype "unspecified"))
      (node (ref "U16") (pin "4") (pinfunction "VSS_4") (pintype "unspecified"))
      (node (ref "U16") (pin "7") (pinfunction "#WC_7") (pintype "unspecified"))
      (node (ref "U2") (pin "2") (pinfunction "V-_2") (pintype "unspecified"))
      (node (ref "U20") (pin "4") (pinfunction "COM_4") (pintype "unspecified"))
      (node (ref "U22") (pin "4") (pinfunction "COM_4") (pintype "unspecified"))
      (node (ref "U23") (pin "2") (pinfunction "V-_2") (pintype "unspecified"))
      (node (ref "U25") (pin "4") (pinfunction "COM_4") (pintype "unspecified"))
      (node (ref "U26") (pin "2") (pinfunction "V-_2") (pintype "unspecified"))
      (node (ref "U28") (pin "4") (pinfunction "COM_4") (pintype "unspecified"))
      (node (ref "U29") (pin "1") (pinfunction "GND_1") (pintype "unspecified"))
      (node (ref "U5") (pin "4") (pinfunction "GND_4") (pintype "unspecified"))
      (node (ref "U5") (pin "8") (pinfunction "DIR_8") (pintype "unspecified"))
      (node (ref "U6") (pin "5") (pinfunction "GND_5") (pintype "unspecified"))
      (node (ref "U7") (pin "5") (pinfunction "GND_5") (pintype "unspecified"))
      (node (ref "X1") (pin "2") (pinfunction "GND_2") (pintype "unspecified"))
      (node (ref "X1") (pin "4") (pinfunction "GND_4") (pintype "unspecified"))
    )
    (net (code "14") (name "INBRAKE") (class "Default")
      (node (ref "R123") (pin "1") (pinfunction "1_1") (pintype "input"))
      (node (ref "R98") (pin "1") (pinfunction "1_1") (pintype "input"))
      (node (ref "U15") (pin "20") (pinfunction "PA6_20") (pintype "unspecified"))
    )
    (net (code "15") (name "INHA") (class "Default")
      (node (ref "R124") (pin "1") (pinfunction "1_1") (pintype "input"))
      (node (ref "U15") (pin "8") (pinfunction "PC0_8") (pintype "unspecified"))
      (node (ref "U20") (pin "2") (pinfunction "HIN_2") (pintype "unspecified"))
    )
    (net (code "16") (name "INHB") (class "Default")
      (node (ref "R125") (pin "1") (pinfunction "1_1") (pintype "input"))
      (node (ref "U15") (pin "9") (pinfunction "PC1_9") (pintype "unspecified"))
      (node (ref "U22") (pin "2") (pinfunction "HIN_2") (pintype "unspecified"))
    )
    (net (code "17") (name "INHC") (class "Default")
      (node (ref "R126") (pin "1") (pinfunction "1_1") (pintype "input"))
      (node (ref "U15") (pin "10") (pinfunction "PC2_10") (pintype "unspecified"))
      (node (ref "U25") (pin "2") (pinfunction "HIN_2") (pintype "unspecified"))
    )
    (net (code "18") (name "INLA") (class "Default")
      (node (ref "U15") (pin "2") (pinfunction "PC13_2") (pintype "unspecified"))
      (node (ref "U20") (pin "3") (pinfunction "LIN_3") (pintype "unspecified"))
    )
    (net (code "19") (name "INLB") (class "Default")
      (node (ref "U15") (pin "24") (pinfunction "PB0_24") (pintype "unspecified"))
      (node (ref "U22") (pin "3") (pinfunction "LIN_3") (pintype "unspecified"))
    )
    (net (code "20") (name "INLC") (class "Default")
      (node (ref "U15") (pin "25") (pinfunction "PB1_25") (pintype "unspecified"))
      (node (ref "U25") (pin "3") (pinfunction "LIN_3") (pintype "unspecified"))
    )
    (net (code "21") (name "NRST") (class "Default")
      (node (ref "C164") (pin "2") (pinfunction "2_2") (pintype "input"))
      (node (ref "J8") (pin "2") (pinfunction "2_2") (pintype "unspecified"))
      (node (ref "R99") (pin "1") (pinfunction "1_1") (pintype "input"))
      (node (ref "U15") (pin "7") (pinfunction "PG10-NRST_7") (pintype "unspecified"))
    )
    (net (code "22") (name "Net-(D3-K)") (class "Default")
      (node (ref "C151") (pin "2") (pinfunction "2_2") (pintype "input"))
      (node (ref "D3") (pin "1") (pinfunction "K_1") (pintype "unspecified"))
      (node (ref "U20") (pin "8") (pinfunction "VB_8") (pintype "unspecified"))
    )
    (net (code "23") (name "Net-(D4-K)") (class "Default")
      (node (ref "C143") (pin "2") (pinfunction "2_2") (pintype "input"))
      (node (ref "D4") (pin "1") (pinfunction "K_1") (pintype "unspecified"))
      (node (ref "U22") (pin "8") (pinfunction "VB_8") (pintype "unspecified"))
    )
    (net (code "24") (name "Net-(D5-K)") (class "Default")
      (node (ref "C145") (pin "2") (pinfunction "2_2") (pintype "input"))
      (node (ref "D5") (pin "1") (pinfunction "K_1") (pintype "unspecified"))
      (node (ref "U25") (pin "8") (pinfunction "VB_8") (pintype "unspecified"))
    )
    (net (code "25") (name "Net-(D6-K)") (class "Default")
      (node (ref "C154") (pin "2") (pinfunction "2_2") (pintype "input"))
      (node (ref "D6") (pin "1") (pinfunction "K_1") (pintype "unspecified"))
      (node (ref "U28") (pin "8") (pinfunction "VB_8") (pintype "unspecified"))
    )
    (net (code "26") (name "Net-(LED1-A)") (class "Default")
      (node (ref "LED1") (pin "2") (pinfunction "A_2") (pintype "unspecified"))
      (node (ref "R108") (pin "2") (pinfunction "2_2") (pintype "input"))
    )
    (net (code "27") (name "Net-(LED2-A)") (class "Default")
      (node (ref "LED2") (pin "2") (pinfunction "A_2") (pintype "unspecified"))
      (node (ref "R109") (pin "2") (pinfunction "2_2") (pintype "input"))
    )
    (net (code "28") (name "Net-(LED3-A)") (class "Default")
      (node (ref "LED3") (pin "2") (pinfunction "A_2") (pintype "unspecified"))
      (node (ref "R110") (pin "2") (pinfunction "2_2") (pintype "input"))
    )
    (net (code "29") (name "Net-(LED4-A)") (class "Default")
      (node (ref "LED4") (pin "2") (pinfunction "A_2") (pintype "unspecified"))
      (node (ref "R111") (pin "2") (pinfunction "2_2") (pintype "input"))
    )
    (net (code "30") (name "Net-(LED5-A)") (class "Default")
      (node (ref "LED5") (pin "2") (pinfunction "A_2") (pintype "unspecified"))
      (node (ref "R112") (pin "2") (pinfunction "2_2") (pintype "input"))
    )
    (net (code "31") (name "Net-(LED6-A)") (class "Default")
      (node (ref "LED6") (pin "2") (pinfunction "A_2") (pintype "unspecified"))
      (node (ref "R113") (pin "2") (pinfunction "2_2") (pintype "input"))
    )
    (net (code "32") (name "Net-(LED7-A)") (class "Default")
      (node (ref "LED7") (pin "2") (pinfunction "A_2") (pintype "unspecified"))
      (node (ref "R114") (pin "2") (pinfunction "2_2") (pintype "input"))
    )
    (net (code "33") (name "Net-(LED8-A)") (class "Default")
      (node (ref "LED8") (pin "2") (pinfunction "A_2") (pintype "unspecified"))
      (node (ref "R115") (pin "2") (pinfunction "2_2") (pintype "input"))
    )
    (net (code "34") (name "Net-(LED9-K)") (class "Default")
      (node (ref "LED9") (pin "1") (pinfunction "K_1") (pintype "unspecified"))
      (node (ref "R117") (pin "2") (pinfunction "2_2") (pintype "input"))
    )
    (net (code "35") (name "Net-(LED10-K)") (class "Default")
      (node (ref "LED10") (pin "1") (pinfunction "K_1") (pintype "unspecified"))
      (node (ref "R118") (pin "2") (pinfunction "2_2") (pintype "input"))
    )
    (net (code "36") (name "Net-(LED11-K)") (class "Default")
      (node (ref "LED11") (pin "1") (pinfunction "K_1") (pintype "unspecified"))
      (node (ref "R119") (pin "2") (pinfunction "2_2") (pintype "input"))
    )
    (net (code "37") (name "Net-(LED12-K)") (class "Default")
      (node (ref "LED12") (pin "1") (pinfunction "K_1") (pintype "unspecified"))
      (node (ref "R120") (pin "2") (pinfunction "2_2") (pintype "input"))
    )
    (net (code "38") (name "Net-(LED13-K)") (class "Default")
      (node (ref "LED13") (pin "1") (pinfunction "K_1") (pintype "unspecified"))
      (node (ref "R121") (pin "2") (pinfunction "2_2") (pintype "input"))
    )
    (net (code "39") (name "Net-(LED14-K)") (class "Default")
      (node (ref "LED14") (pin "1") (pinfunction "K_1") (pintype "unspecified"))
      (node (ref "R122") (pin "2") (pinfunction "2_2") (pintype "input"))
    )
    (net (code "40") (name "Net-(LED15-A)") (class "Default")
      (node (ref "LED15") (pin "2") (pinfunction "A_2") (pintype "unspecified"))
      (node (ref "R123") (pin "2") (pinfunction "2_2") (pintype "input"))
    )
    (net (code "41") (name "Net-(LED16-A)") (class "Default")
      (node (ref "LED16") (pin "2") (pinfunction "A_2") (pintype "unspecified"))
      (node (ref "R124") (pin "2") (pinfunction "2_2") (pintype "input"))
    )
    (net (code "42") (name "Net-(LED17-A)") (class "Default")
      (node (ref "LED17") (pin "2") (pinfunction "A_2") (pintype "unspecified"))
      (node (ref "R125") (pin "2") (pinfunction "2_2") (pintype "input"))
    )
    (net (code "43") (name "Net-(LED18-A)") (class "Default")
      (node (ref "LED18") (pin "2") (pinfunction "A_2") (pintype "unspecified"))
      (node (ref "R126") (pin "2") (pinfunction "2_2") (pintype "input"))
    )
    (net (code "44") (name "Net-(Q1-G)") (class "Default")
      (node (ref "Q1") (pin "1") (pinfunction "G_1") (pintype "unspecified"))
      (node (ref "R71") (pin "2") (pinfunction "2_2") (pintype "input"))
    )
    (net (code "45") (name "Net-(Q2-G)") (class "Default")
      (node (ref "Q2") (pin "1") (pinfunction "G_1") (pintype "unspecified"))
      (node (ref "R72") (pin "2") (pinfunction "2_2") (pintype "input"))
    )
    (net (code "46") (name "Net-(Q2-S)") (class "Default")
      (node (ref "Q2") (pin "3") (pinfunction "S_3") (pintype "unspecified"))
      (node (ref "R1") (pin "2") (pinfunction "2_2") (pintype "unspecified"))
      (node (ref "R85") (pin "2") (pinfunction "2_2") (pintype "input"))
    )
    (net (code "47") (name "Net-(Q7-G)") (class "Default")
      (node (ref "Q7") (pin "1") (pinfunction "G_1") (pintype "unspecified"))
      (node (ref "R73") (pin "2") (pinfunction "2_2") (pintype "input"))
    )
    (net (code "48") (name "Net-(Q8-G)") (class "Default")
      (node (ref "Q8") (pin "1") (pinfunction "G_1") (pintype "unspecified"))
      (node (ref "R74") (pin "2") (pinfunction "2_2") (pintype "input"))
    )
    (net (code "49") (name "Net-(Q8-S)") (class "Default")
      (node (ref "Q8") (pin "3") (pinfunction "S_3") (pintype "unspecified"))
      (node (ref "R47") (pin "2") (pinfunction "2_2") (pintype "unspecified"))
      (node (ref "R87") (pin "2") (pinfunction "2_2") (pintype "input"))
    )
    (net (code "50") (name "Net-(Q9-G)") (class "Default")
      (node (ref "Q9") (pin "1") (pinfunction "G_1") (pintype "unspecified"))
      (node (ref "R75") (pin "2") (pinfunction "2_2") (pintype "input"))
    )
    (net (code "51") (name "Net-(Q10-G)") (class "Default")
      (node (ref "Q10") (pin "1") (pinfunction "G_1") (pintype "unspecified"))
      (node (ref "R76") (pin "2") (pinfunction "2_2") (pintype "input"))
    )
    (net (code "52") (name "Net-(Q10-S)") (class "Default")
      (node (ref "Q10") (pin "3") (pinfunction "S_3") (pintype "unspecified"))
      (node (ref "R54") (pin "2") (pinfunction "2_2") (pintype "unspecified"))
      (node (ref "R89") (pin "2") (pinfunction "2_2") (pintype "input"))
    )
    (net (code "53") (name "Net-(Q12-G)") (class "Default")
      (node (ref "Q12") (pin "1") (pinfunction "G_1") (pintype "unspecified"))
      (node (ref "R77") (pin "2") (pinfunction "2_2") (pintype "input"))
    )
    (net (code "54") (name "Net-(R91-Pad1)") (class "Default")
      (node (ref "R91") (pin "1") (pinfunction "1_1") (pintype "input"))
      (node (ref "R93") (pin "2") (pinfunction "2_2") (pintype "input"))
    )
    (net (code "55") (name "Net-(U2A-IN+)") (class "Default")
      (node (ref "R6") (pin "1") (pinfunction "1_1") (pintype "input"))
      (node (ref "R82") (pin "1") (pinfunction "1_1") (pintype "input"))
      (node (ref "R85") (pin "1") (pinfunction "1_1") (pintype "input"))
      (node (ref "U2") (pin "3") (pinfunction "IN+_3") (pintype "unspecified"))
    )
    (net (code "56") (name "Net-(U2A-IN-)") (class "Default")
      (node (ref "R5") (pin "1") (pinfunction "1_1") (pintype "input"))
      (node (ref "R86") (pin "1") (pinfunction "1_1") (pintype "input"))
      (node (ref "U2") (pin "4") (pinfunction "IN-_4") (pintype "unspecified"))
    )
    (net (code "57") (name "Net-(U2A-OUT)") (class "Default")
      (node (ref "R5") (pin "2") (pinfunction "2_2") (pintype "input"))
      (node (ref "R94") (pin "2") (pinfunction "2_2") (pintype "input"))
      (node (ref "U2") (pin "1") (pinfunction "OUT_1") (pintype "unspecified"))
    )
    (net (code "58") (name "Net-(U5-OUT)") (class "Default")
      (node (ref "R107") (pin "1") (pinfunction "1_1") (pintype "input"))
      (node (ref "U5") (pin "3") (pinfunction "OUT_3") (pintype "unspecified"))
    )
    (net (code "59") (name "Net-(U12-BOOT)") (class "Default")
      (node (ref "C138") (pin "2") (pinfunction "2_2") (pintype "input"))
      (node (ref "U12") (pin "6") (pinfunction "BOOT_6") (pintype "unspecified"))
    )
    (net (code "60") (name "Net-(U12-FB)") (class "Default")
      (node (ref "C109") (pin "1") (pinfunction "1_1") (pintype "input"))
      (node (ref "R31") (pin "2") (pinfunction "2_2") (pintype "input"))
      (node (ref "R39") (pin "1") (pinfunction "1_1") (pintype "input"))
      (node (ref "U12") (pin "4") (pinfunction "FB_4") (pintype "unspecified"))
    )
    (net (code "61") (name "Net-(U12-SW)") (class "Default")
      (node (ref "C138") (pin "1") (pinfunction "1_1") (pintype "input"))
      (node (ref "L1") (pin "1") (pinfunction "1_1") (pintype "unspecified"))
      (node (ref "U12") (pin "2") (pinfunction "SW_2") (pintype "unspecified"))
    )
    (net (code "62") (name "Net-(U15-PA8)") (class "Default")
      (node (ref "R103") (pin "1") (pinfunction "1_1") (pintype "input"))
      (node (ref "U15") (pin "42") (pinfunction "PA8_42") (pintype "unspecified"))
      (node (ref "U16") (pin "5") (pinfunction "SDA_5") (pintype "bidirectional"))
    )
    (net (code "63") (name "Net-(U15-PA9)") (class "Default")
      (node (ref "R102") (pin "1") (pinfunction "1_1") (pintype "input"))
      (node (ref "U15") (pin "43") (pinfunction "PA9_43") (pintype "unspecified"))
      (node (ref "U16") (pin "6") (pinfunction "SCL_6") (pintype "unspecified"))
    )
    (net (code "64") (name "Net-(U15-PA12)") (class "Default")
      (node (ref "R101") (pin "2") (pinfunction "2_2") (pintype "input"))
      (node (ref "U15") (pin "46") (pinfunction "PA12_46") (pintype "unspecified"))
      (node (ref "U6") (pin "2") (pinfunction "RE#_2") (pintype "unspecified"))
      (node (ref "U6") (pin "3") (pinfunction "DE_3") (pintype "unspecified"))
    )
    (net (code "65") (name "Net-(U15-PB2)") (class "Default")
      (node (ref "R108") (pin "1") (pinfunction "1_1") (pintype "input"))
      (node (ref "U15") (pin "26") (pinfunction "PB2_26") (pintype "unspecified"))
    )
    (net (code "66") (name "Net-(U15-PB3)") (class "Default")
      (node (ref "R109") (pin "1") (pinfunction "1_1") (pintype "input"))
      (node (ref "U15") (pin "56") (pinfunction "PB3_56") (pintype "unspecified"))
    )
    (net (code "67") (name "Net-(U15-PB4)") (class "Default")
      (node (ref "R110") (pin "1") (pinfunction "1_1") (pintype "input"))
      (node (ref "U15") (pin "57") (pinfunction "PB4_57") (pintype "unspecified"))
    )
    (net (code "68") (name "Net-(U15-PB5)") (class "Default")
      (node (ref "R111") (pin "1") (pinfunction "1_1") (pintype "input"))
      (node (ref "U15") (pin "58") (pinfunction "PB5_58") (pintype "unspecified"))
    )
    (net (code "69") (name "Net-(U15-PB6)") (class "Default")
      (node (ref "R112") (pin "1") (pinfunction "1_1") (pintype "input"))
      (node (ref "U15") (pin "59") (pinfunction "PB6_59") (pintype "unspecified"))
    )
    (net (code "70") (name "Net-(U15-PB7)") (class "Default")
      (node (ref "R113") (pin "1") (pinfunction "1_1") (pintype "input"))
      (node (ref "U15") (pin "60") (pinfunction "PB7_60") (pintype "unspecified"))
    )
    (net (code "71") (name "Net-(U15-PB8-BOOT0)") (class "Default")
      (node (ref "R106") (pin "2") (pinfunction "2_2") (pintype "input"))
      (node (ref "U15") (pin "61") (pinfunction "PB8-BOOT0_61") (pintype "unspecified"))
    )
    (net (code "72") (name "Net-(U15-PB9)") (class "Default")
      (node (ref "R114") (pin "1") (pinfunction "1_1") (pintype "input"))
      (node (ref "U15") (pin "62") (pinfunction "PB9_62") (pintype "unspecified"))
    )
    (net (code "73") (name "Net-(U15-PB10)") (class "Default")
      (node (ref "R120") (pin "1") (pinfunction "1_1") (pintype "input"))
      (node (ref "U15") (pin "30") (pinfunction "PB10_30") (pintype "unspecified"))
      (node (ref "U7") (pin "1") (pinfunction "RO_1") (pintype "unspecified"))
    )
    (net (code "74") (name "Net-(U15-PB11)") (class "Default")
      (node (ref "R119") (pin "1") (pinfunction "1_1") (pintype "input"))
      (node (ref "U15") (pin "33") (pinfunction "PB11_33") (pintype "unspecified"))
      (node (ref "U7") (pin "4") (pinfunction "DI_4") (pintype "unspecified"))
    )
    (net (code "75") (name "Net-(U15-PB12)") (class "Default")
      (node (ref "C4") (pin "2") (pinfunction "2_2") (pintype "input"))
      (node (ref "R107") (pin "2") (pinfunction "2_2") (pintype "input"))
      (node (ref "U15") (pin "34") (pinfunction "PB12_34") (pintype "unspecified"))
    )
    (net (code "76") (name "Net-(U15-PB13)") (class "Default")
      (node (ref "R115") (pin "1") (pinfunction "1_1") (pintype "input"))
      (node (ref "U15") (pin "35") (pinfunction "PB13_35") (pintype "unspecified"))
    )
    (net (code "77") (name "Net-(U15-PB14)") (class "Default")
      (node (ref "R100") (pin "2") (pinfunction "2_2") (pintype "input"))
      (node (ref "U15") (pin "36") (pinfunction "PB14_36") (pintype "unspecified"))
      (node (ref "U7") (pin "2") (pinfunction "RE#_2") (pintype "unspecified"))
      (node (ref "U7") (pin "3") (pinfunction "DE_3") (pintype "unspecified"))
    )
    (net (code "78") (name "Net-(U15-PC4)") (class "Default")
      (node (ref "R118") (pin "1") (pinfunction "1_1") (pintype "input"))
      (node (ref "U15") (pin "22") (pinfunction "PC4_22") (pintype "unspecified"))
      (node (ref "U6") (pin "1") (pinfunction "RO_1") (pintype "unspecified"))
    )
    (net (code "79") (name "Net-(U15-PC5)") (class "Default")
      (node (ref "R117") (pin "1") (pinfunction "1_1") (pintype "input"))
      (node (ref "U15") (pin "23") (pinfunction "PC5_23") (pintype "unspecified"))
      (node (ref "U6") (pin "4") (pinfunction "DI_4") (pintype "unspecified"))
    )
    (net (code "80") (name "Net-(U15-PC8)") (class "Default")
      (node (ref "R104") (pin "1") (pinfunction "1_1") (pintype "input"))
      (node (ref "U15") (pin "40") (pinfunction "PC8_40") (pintype "unspecified"))
      (node (ref "U5") (pin "7") (pinfunction "SCL_7") (pintype "unspecified"))
    )
    (net (code "81") (name "Net-(U15-PC9)") (class "Default")
      (node (ref "R105") (pin "1") (pinfunction "1_1") (pintype "input"))
      (node (ref "U15") (pin "41") (pinfunction "PC9_41") (pintype "unspecified"))
      (node (ref "U5") (pin "6") (pinfunction "SDA_6") (pintype "unspecified"))
    )
    (net (code "82") (name "Net-(U15-PF0-OSC_IN)") (class "Default")
      (node (ref "C47") (pin "2") (pinfunction "2_2") (pintype "unspecified"))
      (node (ref "U15") (pin "5") (pinfunction "PF0-OSC_IN_5") (pintype "unspecified"))
      (node (ref "X1") (pin "1") (pinfunction "OSC1_1") (pintype "unspecified"))
    )
    (net (code "83") (name "Net-(U15-PF1-OSC_OUT)") (class "Default")
      (node (ref "C46") (pin "2") (pinfunction "2_2") (pintype "unspecified"))
      (node (ref "U15") (pin "6") (pinfunction "PF1-OSC_OUT_6") (pintype "unspecified"))
      (node (ref "X1") (pin "3") (pinfunction "OSC2_3") (pintype "unspecified"))
    )
    (net (code "84") (name "Net-(U20-HO)") (class "Default")
      (node (ref "R71") (pin "1") (pinfunction "1_1") (pintype "input"))
      (node (ref "U20") (pin "7") (pinfunction "HO_7") (pintype "unspecified"))
    )
    (net (code "85") (name "Net-(U20-LO)") (class "Default")
      (node (ref "R72") (pin "1") (pinfunction "1_1") (pintype "input"))
      (node (ref "U20") (pin "5") (pinfunction "LO_5") (pintype "unspecified"))
    )
    (net (code "86") (name "Net-(U22-HO)") (class "Default")
      (node (ref "R73") (pin "1") (pinfunction "1_1") (pintype "input"))
      (node (ref "U22") (pin "7") (pinfunction "HO_7") (pintype "unspecified"))
    )
    (net (code "87") (name "Net-(U22-LO)") (class "Default")
      (node (ref "R74") (pin "1") (pinfunction "1_1") (pintype "input"))
      (node (ref "U22") (pin "5") (pinfunction "LO_5") (pintype "unspecified"))
    )
    (net (code "88") (name "Net-(U23A-IN+)") (class "Default")
      (node (ref "R45") (pin "1") (pinfunction "1_1") (pintype "input"))
      (node (ref "R83") (pin "1") (pinfunction "1_1") (pintype "input"))
      (node (ref "R87") (pin "1") (pinfunction "1_1") (pintype "input"))
      (node (ref "U23") (pin "3") (pinfunction "IN+_3") (pintype "unspecified"))
    )
    (net (code "89") (name "Net-(U23A-IN-)") (class "Default")
      (node (ref "R44") (pin "1") (pinfunction "1_1") (pintype "input"))
      (node (ref "R88") (pin "1") (pinfunction "1_1") (pintype "input"))
      (node (ref "U23") (pin "4") (pinfunction "IN-_4") (pintype "unspecified"))
    )
    (net (code "90") (name "Net-(U23A-OUT)") (class "Default")
      (node (ref "R44") (pin "2") (pinfunction "2_2") (pintype "input"))
      (node (ref "R95") (pin "2") (pinfunction "2_2") (pintype "input"))
      (node (ref "U23") (pin "1") (pinfunction "OUT_1") (pintype "unspecified"))
    )
    (net (code "91") (name "Net-(U25-HO)") (class "Default")
      (node (ref "R75") (pin "1") (pinfunction "1_1") (pintype "input"))
      (node (ref "U25") (pin "7") (pinfunction "HO_7") (pintype "unspecified"))
    )
    (net (code "92") (name "Net-(U25-LO)") (class "Default")
      (node (ref "R76") (pin "1") (pinfunction "1_1") (pintype "input"))
      (node (ref "U25") (pin "5") (pinfunction "LO_5") (pintype "unspecified"))
    )
    (net (code "93") (name "Net-(U26A-IN+)") (class "Default")
      (node (ref "R52") (pin "1") (pinfunction "1_1") (pintype "input"))
      (node (ref "R84") (pin "1") (pinfunction "1_1") (pintype "input"))
      (node (ref "R89") (pin "1") (pinfunction "1_1") (pintype "input"))
      (node (ref "U26") (pin "3") (pinfunction "IN+_3") (pintype "unspecified"))
    )
    (net (code "94") (name "Net-(U26A-IN-)") (class "Default")
      (node (ref "R51") (pin "1") (pinfunction "1_1") (pintype "input"))
      (node (ref "R90") (pin "1") (pinfunction "1_1") (pintype "input"))
      (node (ref "U26") (pin "4") (pinfunction "IN-_4") (pintype "unspecified"))
    )
    (net (code "95") (name "Net-(U26A-OUT)") (class "Default")
      (node (ref "R51") (pin "2") (pinfunction "2_2") (pintype "input"))
      (node (ref "R96") (pin "2") (pinfunction "2_2") (pintype "input"))
      (node (ref "U26") (pin "1") (pinfunction "OUT_1") (pintype "unspecified"))
    )
    (net (code "96") (name "Net-(U28-HIN)") (class "Default")
      (node (ref "R97") (pin "1") (pinfunction "1_1") (pintype "input"))
      (node (ref "U28") (pin "2") (pinfunction "HIN_2") (pintype "unspecified"))
    )
    (net (code "97") (name "Net-(U28-LIN)") (class "Default")
      (node (ref "R98") (pin "2") (pinfunction "2_2") (pintype "input"))
      (node (ref "U28") (pin "3") (pinfunction "LIN_3") (pintype "unspecified"))
    )
    (net (code "98") (name "Net-(U28-LO)") (class "Default")
      (node (ref "R77") (pin "1") (pinfunction "1_1") (pintype "input"))
      (node (ref "U28") (pin "5") (pinfunction "LO_5") (pintype "unspecified"))
    )
    (net (code "99") (name "Net-(U29-BOOT)") (class "Default")
      (node (ref "C137") (pin "2") (pinfunction "2_2") (pintype "input"))
      (node (ref "U29") (pin "6") (pinfunction "BOOT_6") (pintype "unspecified"))
    )
    (net (code "100") (name "Net-(U29-FB)") (class "Default")
      (node (ref "C54") (pin "1") (pinfunction "1_1") (pintype "input"))
      (node (ref "R80") (pin "1") (pinfunction "1_1") (pintype "input"))
      (node (ref "R81") (pin "2") (pinfunction "2_2") (pintype "input"))
      (node (ref "U29") (pin "4") (pinfunction "FB_4") (pintype "unspecified"))
    )
    (net (code "101") (name "Net-(U29-SW)") (class "Default")
      (node (ref "C137") (pin "1") (pinfunction "1_1") (pintype "input"))
      (node (ref "L2") (pin "1") (pinfunction "1_1") (pintype "input"))
      (node (ref "U29") (pin "2") (pinfunction "SW_2") (pintype "unspecified"))
    )
    (net (code "102") (name "OUT_A") (class "Default")
      (node (ref "C151") (pin "1") (pinfunction "1_1") (pintype "input"))
      (node (ref "J1") (pin "1") (pinfunction "1_1") (pintype "unspecified"))
      (node (ref "J1") (pin "2") (pinfunction "2_2") (pintype "unspecified"))
      (node (ref "J1") (pin "3") (pinfunction "3_3") (pintype "unspecified"))
      (node (ref "J1") (pin "4") (pinfunction "4_4") (pintype "unspecified"))
      (node (ref "Q1") (pin "3") (pinfunction "S_3") (pintype "unspecified"))
      (node (ref "Q2") (pin "2") (pinfunction "D_2") (pintype "unspecified"))
      (node (ref "U20") (pin "6") (pinfunction "VS_6") (pintype "unspecified"))
    )
    (net (code "103") (name "OUT_B") (class "Default")
      (node (ref "C143") (pin "1") (pinfunction "1_1") (pintype "input"))
      (node (ref "J2") (pin "1") (pinfunction "1_1") (pintype "unspecified"))
      (node (ref "J2") (pin "2") (pinfunction "2_2") (pintype "unspecified"))
      (node (ref "J2") (pin "3") (pinfunction "3_3") (pintype "unspecified"))
      (node (ref "J2") (pin "4") (pinfunction "4_4") (pintype "unspecified"))
      (node (ref "Q7") (pin "3") (pinfunction "S_3") (pintype "unspecified"))
      (node (ref "Q8") (pin "2") (pinfunction "D_2") (pintype "unspecified"))
      (node (ref "U22") (pin "6") (pinfunction "VS_6") (pintype "unspecified"))
    )
    (net (code "104") (name "OUT_BRAKE") (class "Default")
      (node (ref "C154") (pin "1") (pinfunction "1_1") (pintype "input"))
      (node (ref "D7") (pin "2") (pinfunction "A_2") (pintype "unspecified"))
      (node (ref "Q12") (pin "2") (pinfunction "D_2") (pintype "unspecified"))
      (node (ref "R69") (pin "1") (pinfunction "1_1") (pintype "unspecified"))
      (node (ref "R70") (pin "1") (pinfunction "1_1") (pintype "unspecified"))
      (node (ref "U28") (pin "6") (pinfunction "VS_6") (pintype "unspecified"))
    )
    (net (code "105") (name "OUT_C") (class "Default")
      (node (ref "C145") (pin "1") (pinfunction "1_1") (pintype "input"))
      (node (ref "J3") (pin "1") (pinfunction "1_1") (pintype "unspecified"))
      (node (ref "J3") (pin "2") (pinfunction "2_2") (pintype "unspecified"))
      (node (ref "J3") (pin "3") (pinfunction "3_3") (pintype "unspecified"))
      (node (ref "J3") (pin "4") (pinfunction "4_4") (pintype "unspecified"))
      (node (ref "Q10") (pin "2") (pinfunction "D_2") (pintype "unspecified"))
      (node (ref "Q9") (pin "3") (pinfunction "S_3") (pintype "unspecified"))
      (node (ref "U25") (pin "6") (pinfunction "VS_6") (pintype "unspecified"))
    )
    (net (code "106") (name "SUPPLY_ADC") (class "Default")
      (node (ref "C126") (pin "2") (pinfunction "2_2") (pintype "input"))
      (node (ref "R91") (pin "2") (pinfunction "2_2") (pintype "input"))
      (node (ref "R92") (pin "1") (pinfunction "1_1") (pintype "input"))
      (node (ref "U15") (pin "17") (pinfunction "PA3_17") (pintype "unspecified"))
    )
    (net (code "107") (name "SWCLK") (class "Default")
      (node (ref "J8") (pin "4") (pinfunction "4_4") (pintype "unspecified"))
      (node (ref "U15") (pin "50") (pinfunction "PA14_50") (pintype "unspecified"))
    )
    (net (code "108") (name "SWDIO") (class "Default")
      (node (ref "J8") (pin "3") (pinfunction "3_3") (pintype "unspecified"))
      (node (ref "U15") (pin "49") (pinfunction "PA13_49") (pintype "unspecified"))
    )
    (net (code "109") (name "unconnected-(J9-Pad1)") (class "Default")
      (node (ref "J9") (pin "1") (pinfunction "1_1") (pintype "unspecified+no_connect"))
    )
    (net (code "110") (name "unconnected-(J9-Pad5)") (class "Default")
      (node (ref "J9") (pin "5") (pinfunction "5_5") (pintype "unspecified+no_connect"))
    )
    (net (code "111") (name "unconnected-(J9-Pad6)") (class "Default")
      (node (ref "J9") (pin "6") (pinfunction "6_6") (pintype "unspecified+no_connect"))
    )
    (net (code "112") (name "unconnected-(U12-EN-Pad5)") (class "Default")
      (node (ref "U12") (pin "5") (pinfunction "EN_5") (pintype "unspecified+no_connect"))
    )
    (net (code "113") (name "unconnected-(U15-PA4-Pad18)") (class "Default")
      (node (ref "U15") (pin "18") (pinfunction "PA4_18") (pintype "unspecified+no_connect"))
    )
    (net (code "114") (name "unconnected-(U15-PA5-Pad19)") (class "Default")
      (node (ref "U15") (pin "19") (pinfunction "PA5_19") (pintype "unspecified+no_connect"))
    )
    (net (code "115") (name "unconnected-(U15-PA7-Pad21)") (class "Default")
      (node (ref "U15") (pin "21") (pinfunction "PA7_21") (pintype "unspecified+no_connect"))
    )
    (net (code "116") (name "unconnected-(U15-PA10-Pad44)") (class "Default")
      (node (ref "U15") (pin "44") (pinfunction "PA10_44") (pintype "unspecified+no_connect"))
    )
    (net (code "117") (name "unconnected-(U15-PA11-Pad45)") (class "Default")
      (node (ref "U15") (pin "45") (pinfunction "PA11_45") (pintype "unspecified+no_connect"))
    )
    (net (code "118") (name "unconnected-(U15-PA15-Pad51)") (class "Default")
      (node (ref "U15") (pin "51") (pinfunction "PA15_51") (pintype "unspecified+no_connect"))
    )
    (net (code "119") (name "unconnected-(U15-PB15-Pad37)") (class "Default")
      (node (ref "U15") (pin "37") (pinfunction "PB15_37") (pintype "unspecified+no_connect"))
    )
    (net (code "120") (name "unconnected-(U15-PC3-Pad11)") (class "Default")
      (node (ref "U15") (pin "11") (pinfunction "PC3_11") (pintype "unspecified+no_connect"))
    )
    (net (code "121") (name "unconnected-(U15-PC6-Pad38)") (class "Default")
      (node (ref "U15") (pin "38") (pinfunction "PC6_38") (pintype "unspecified+no_connect"))
    )
    (net (code "122") (name "unconnected-(U15-PC7-Pad39)") (class "Default")
      (node (ref "U15") (pin "39") (pinfunction "PC7_39") (pintype "unspecified+no_connect"))
    )
    (net (code "123") (name "unconnected-(U15-PC12-Pad54)") (class "Default")
      (node (ref "U15") (pin "54") (pinfunction "PC12_54") (pintype "unspecified+no_connect"))
    )
    (net (code "124") (name "unconnected-(U15-PC14-OSC32_IN-Pad3)") (class "Default")
      (node (ref "U15") (pin "3") (pinfunction "PC14-OSC32_IN_3") (pintype "unspecified+no_connect"))
    )
    (net (code "125") (name "unconnected-(U15-PC15-OSC32_OUT-Pad4)") (class "Default")
      (node (ref "U15") (pin "4") (pinfunction "PC15-OSC32_OUT_4") (pintype "unspecified+no_connect"))
    )
    (net (code "126") (name "unconnected-(U15-PD2-Pad55)") (class "Default")
      (node (ref "U15") (pin "55") (pinfunction "PD2_55") (pintype "unspecified+no_connect"))
    )
    (net (code "127") (name "unconnected-(U28-HO-Pad7)") (class "Default")
      (node (ref "U28") (pin "7") (pinfunction "HO_7") (pintype "unspecified+no_connect"))
    )
    (net (code "128") (name "unconnected-(U29-EN-Pad5)") (class "Default")
      (node (ref "U29") (pin "5") (pinfunction "EN_5") (pintype "unspecified+no_connect"))
    )
  )
)
